# DSP_Lab_SS21_Mainboard.net
KiCad netlist of a schematic drawn in EAGLE
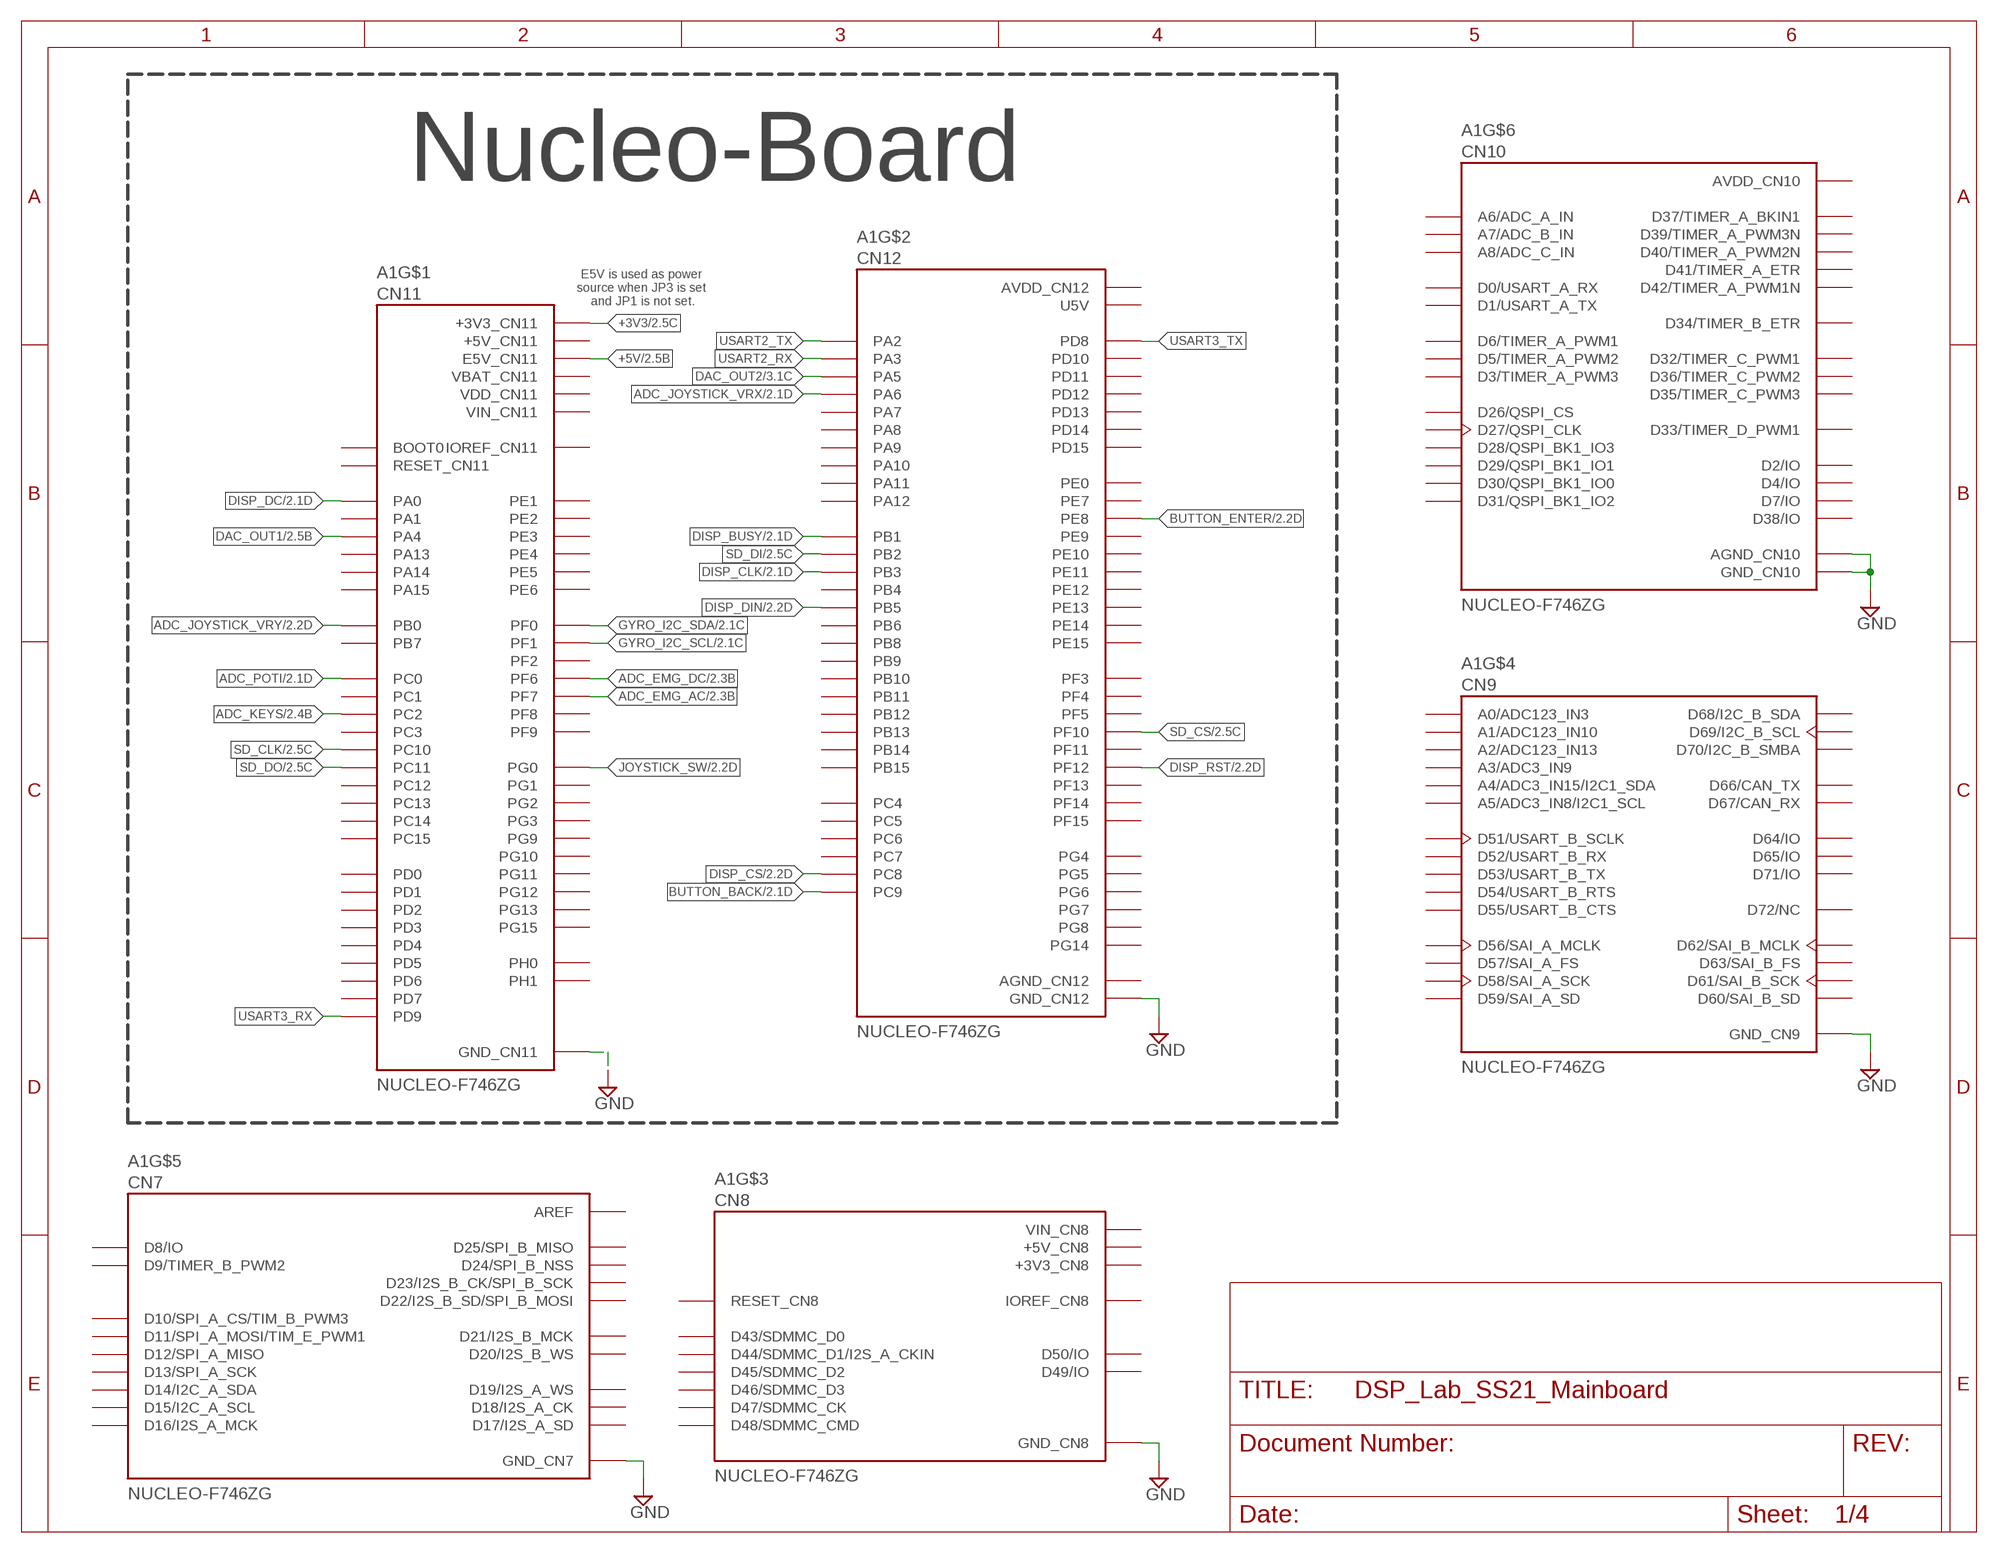
[diagram p0: schematic, sheet 1]
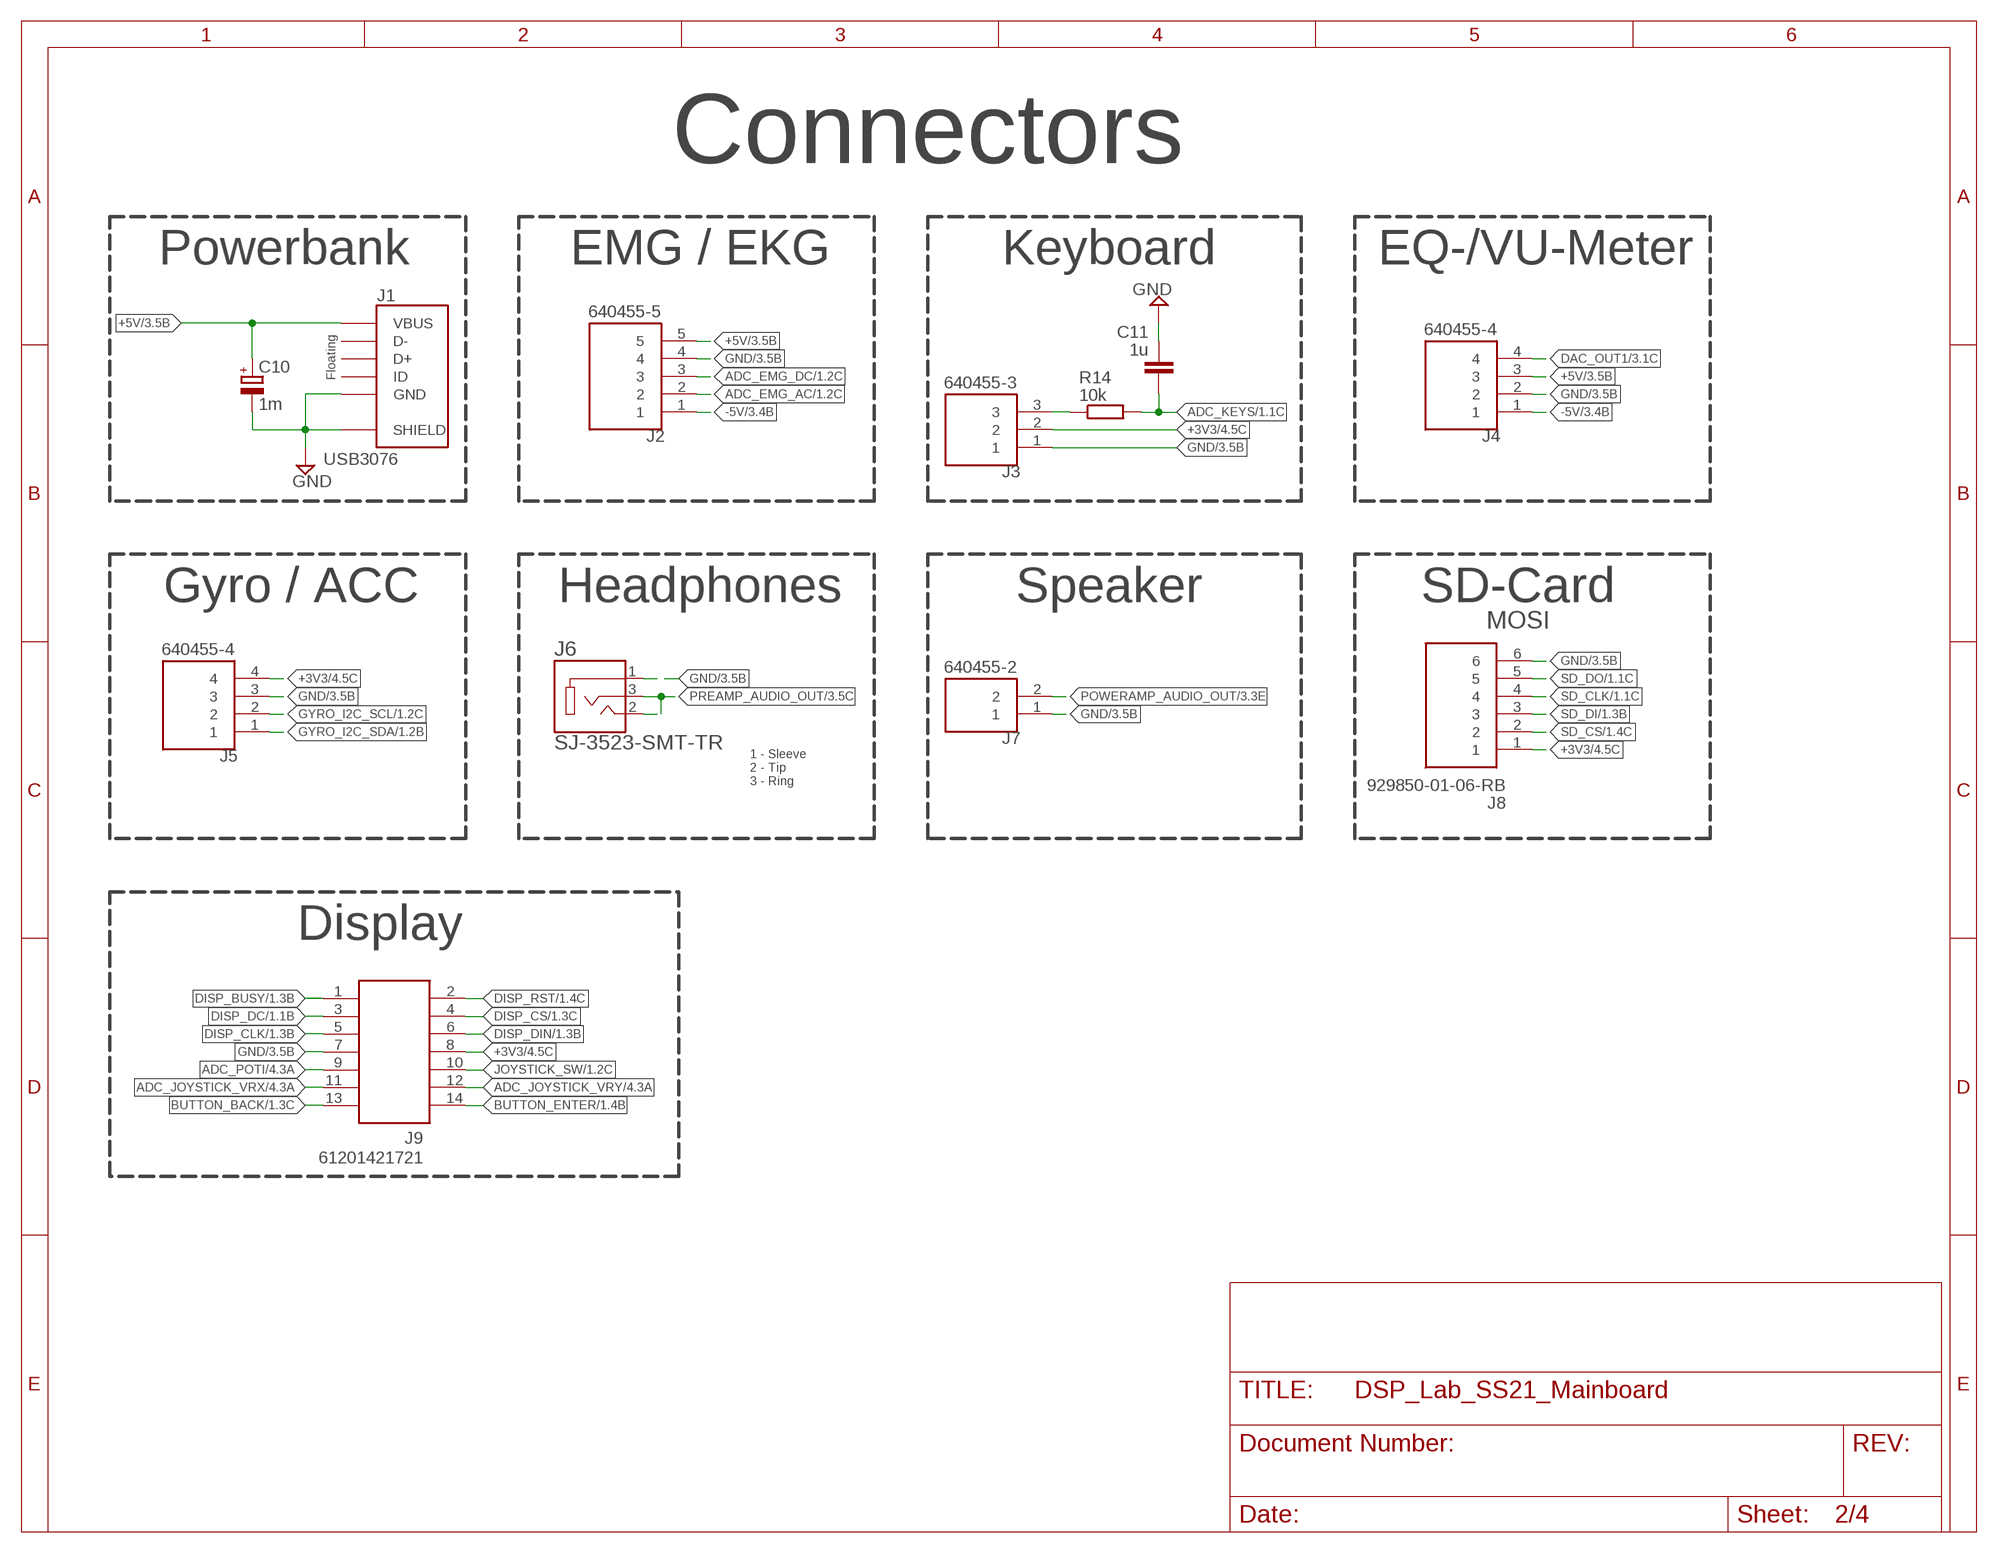
[diagram p1: schematic, sheet 2]
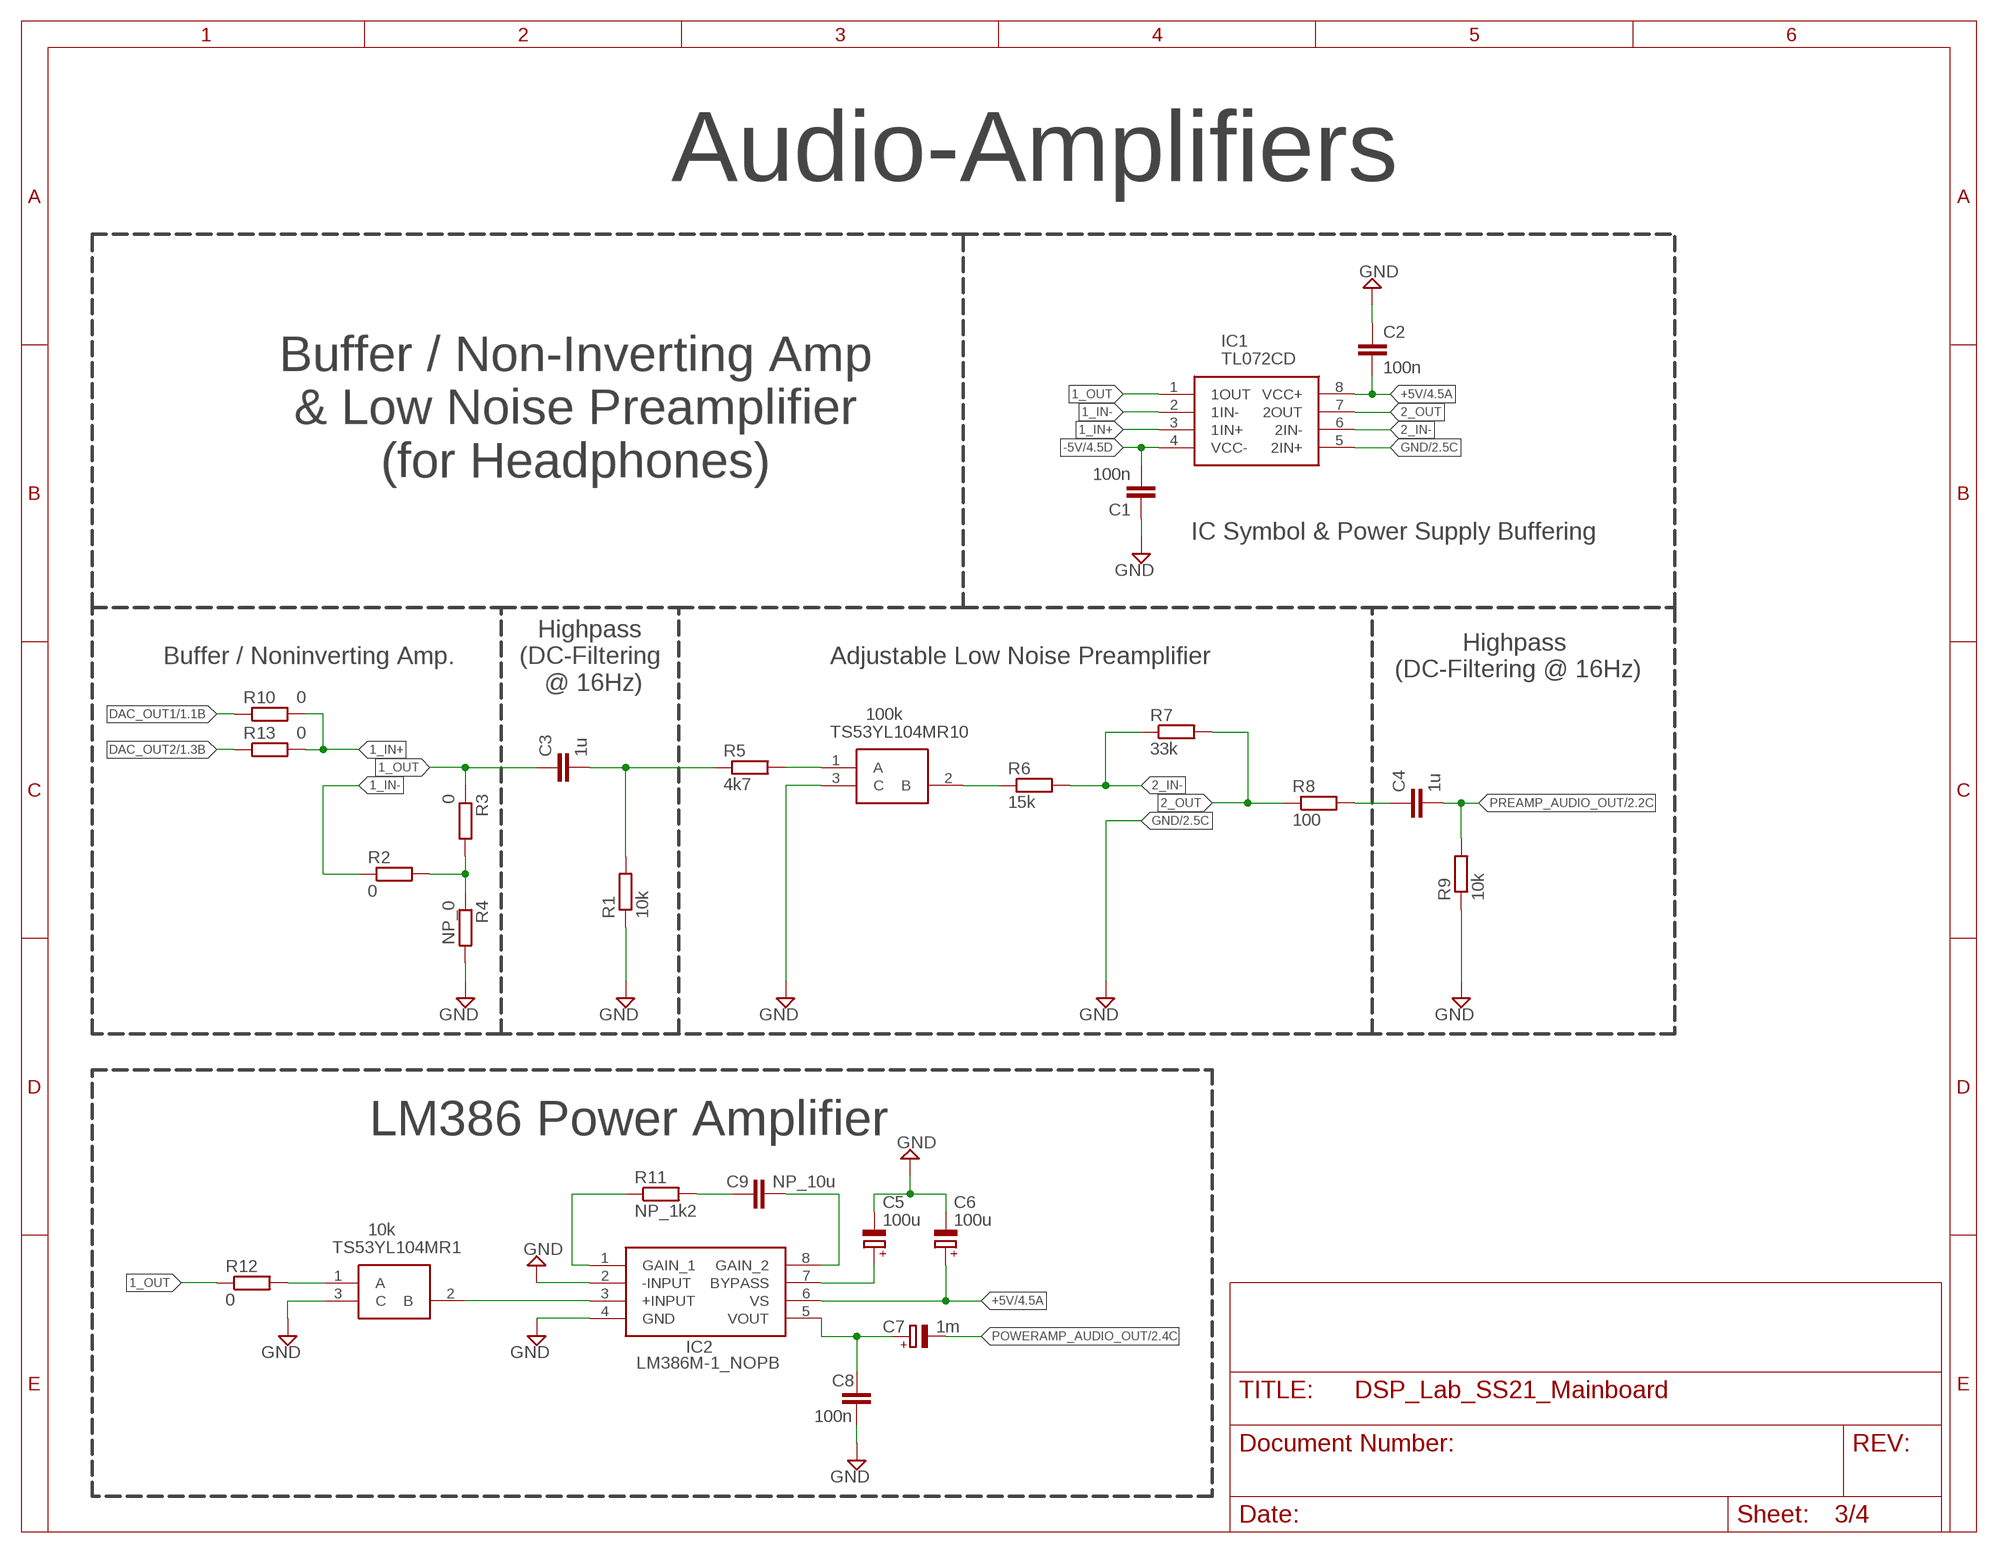
[diagram p2: schematic, sheet 3]
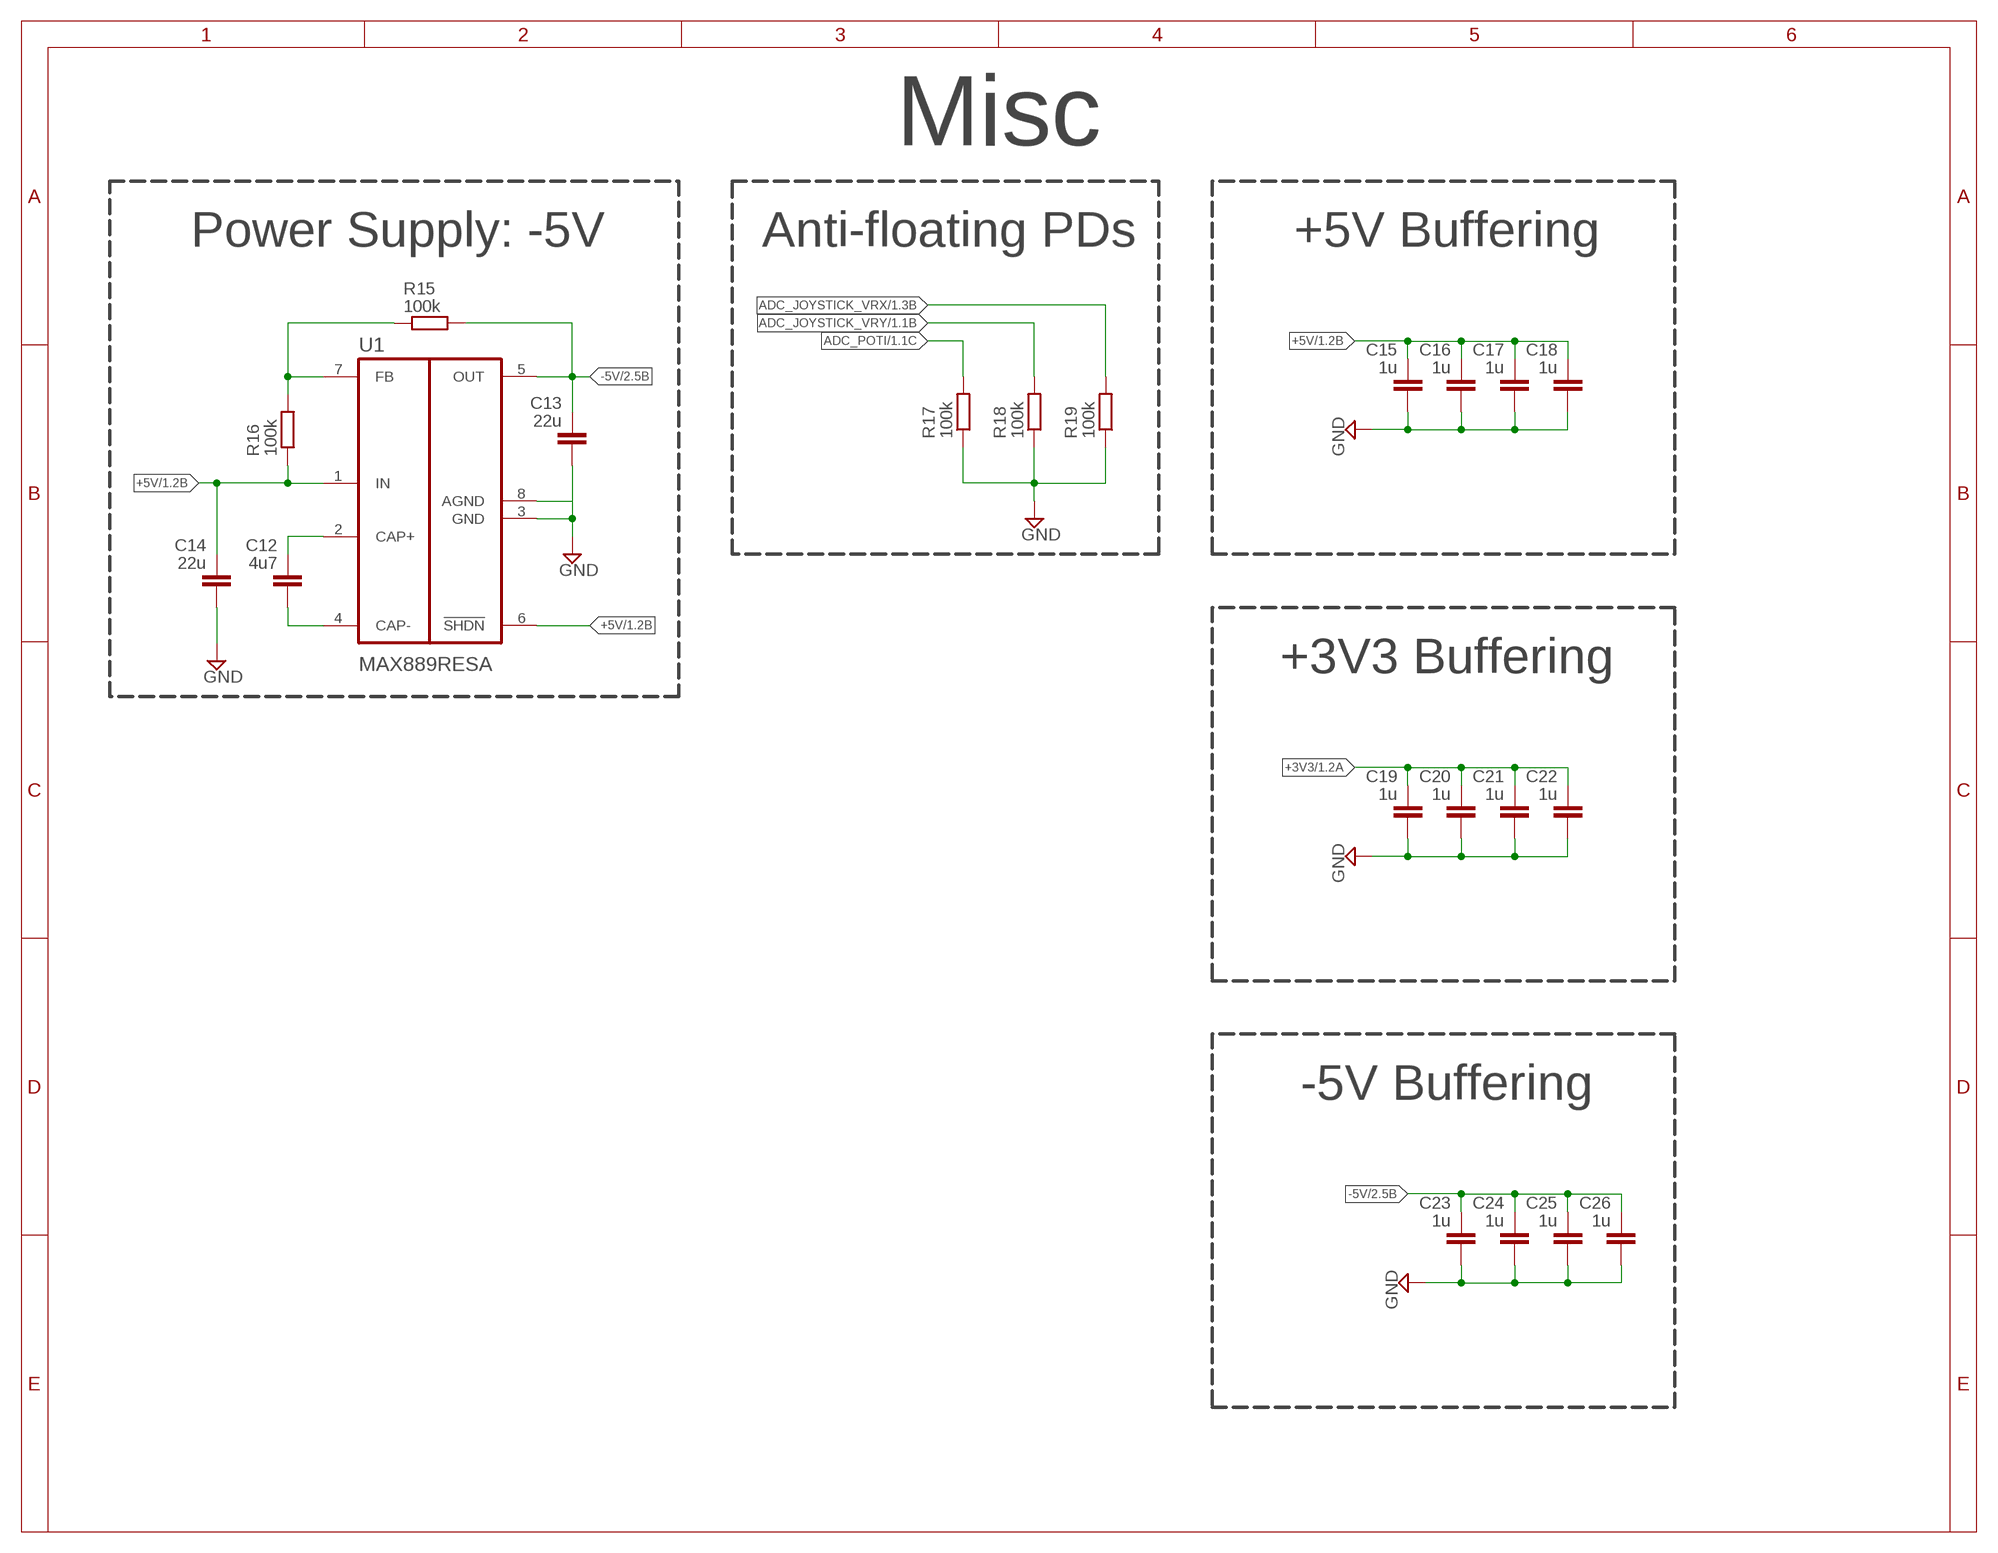
[diagram p3: schematic, sheet 4]

(export (version "E")
  (design (tool "Eeschema 10.0.6"))
  (components
    (comp (ref "C1")
      (value "100n")
      (footprint "eagle-import:C0603")
      (libsource (lib "eagle-import") (part "C-EUC0603"))
    )
    (comp (ref "C2")
      (value "100n")
      (footprint "eagle-import:C0603")
      (libsource (lib "eagle-import") (part "C-EUC0603"))
    )
    (comp (ref "C3")
      (value "1u")
      (footprint "eagle-import:C0603")
      (libsource (lib "eagle-import") (part "C-EUC0603"))
    )
    (comp (ref "C4")
      (value "1u")
      (footprint "eagle-import:C0603")
      (libsource (lib "eagle-import") (part "C-EUC0603"))
    )
    (comp (ref "C5")
      (value "100u")
      (footprint "eagle-import:E2,5-5")
      (libsource (lib "eagle-import") (part "CPOL-EUE2.5-5"))
    )
    (comp (ref "C6")
      (value "100u")
      (footprint "eagle-import:E2,5-5")
      (libsource (lib "eagle-import") (part "CPOL-EUE2.5-5"))
    )
    (comp (ref "C7")
      (value "1m")
      (footprint "eagle-import:E2,5-5")
      (libsource (lib "eagle-import") (part "CPOL-EUE2.5-5"))
    )
    (comp (ref "C8")
      (value "100n")
      (footprint "eagle-import:C0603")
      (libsource (lib "eagle-import") (part "C-EUC0603"))
    )
    (comp (ref "C9")
      (value "NP_10u")
      (footprint "eagle-import:C0603")
      (libsource (lib "eagle-import") (part "C-EUC0603"))
    )
    (comp (ref "IC1")
      (value "TL072CD")
      (footprint "eagle-import:SOIC127P600X175-8N")
      (fields (field (name "MOUSER_PART_NUMBER") "595-TL072CD"))
      (libsource (lib "eagle-import") (part "TL072CD"))
    )
    (comp (ref "IC2")
      (value "LM386M-1_NOPB")
      (footprint "eagle-import:SOIC127P600X175-8N")
      (fields
        (field (name "MANUFACTURER_PART_NUMBER") "LM386M-1/NOPB")
        (field (name "MOUSER_PART_NUMBER") "926-LM386M-1/NOPB")
      )
      (libsource (lib "eagle-import") (part "LM386M-1_NOPB"))
    )
    (comp (ref "R1")
      (value "10k")
      (footprint "eagle-import:R0603")
      (libsource (lib "eagle-import") (part "R-EU_R0603"))
    )
    (comp (ref "R2")
      (value "0")
      (footprint "eagle-import:R0603")
      (libsource (lib "eagle-import") (part "R-EU_R0603"))
    )
    (comp (ref "R3")
      (value "0")
      (footprint "eagle-import:R0603")
      (libsource (lib "eagle-import") (part "R-EU_R0603"))
    )
    (comp (ref "R4")
      (value "NP_0")
      (footprint "eagle-import:R0603")
      (libsource (lib "eagle-import") (part "R-EU_R0603"))
    )
    (comp (ref "R5")
      (value "4k7")
      (footprint "eagle-import:R0603")
      (libsource (lib "eagle-import") (part "R-EU_R0603"))
    )
    (comp (ref "R6")
      (value "15k")
      (footprint "eagle-import:R0603")
      (libsource (lib "eagle-import") (part "R-EU_R0603"))
    )
    (comp (ref "R7")
      (value "33k")
      (footprint "eagle-import:R0603")
      (libsource (lib "eagle-import") (part "R-EU_R0603"))
    )
    (comp (ref "R8")
      (value "100")
      (footprint "eagle-import:R0603")
      (libsource (lib "eagle-import") (part "R-EU_R0603"))
    )
    (comp (ref "R9")
      (value "10k")
      (footprint "eagle-import:R0603")
      (libsource (lib "eagle-import") (part "R-EU_R0603"))
    )
    (comp (ref "R10")
      (value "0")
      (footprint "eagle-import:R0603")
      (libsource (lib "eagle-import") (part "R-EU_R0603"))
    )
    (comp (ref "R11")
      (value "NP_1k2")
      (footprint "eagle-import:R0603")
      (libsource (lib "eagle-import") (part "R-EU_R0603"))
    )
    (comp (ref "R12")
      (value "0")
      (footprint "eagle-import:R0603")
      (libsource (lib "eagle-import") (part "R-EU_R0603"))
    )
    (comp (ref "R13")
      (value "0")
      (footprint "eagle-import:R0603")
      (libsource (lib "eagle-import") (part "R-EU_R0603"))
    )
    (comp (ref "TS53YL104MR1")
      (value "10k")
      (footprint "eagle-import:TS53YL203MR10")
      (fields
        (field (name "MANUFACTURER_PART_NUMBER") "TS53YL203MR10")
        (field (name "MOUSER_PART_NUMBER") "72-TS53YL-20K")
      )
      (libsource (lib "eagle-import") (part "TS53YL203MR10"))
    )
    (comp (ref "TS53YL104MR10")
      (value "100k")
      (footprint "eagle-import:TS53YL203MR10")
      (fields
        (field (name "MANUFACTURER_PART_NUMBER") "TS53YL203MR10")
        (field (name "MOUSER_PART_NUMBER") "72-TS53YL-20K")
      )
      (libsource (lib "eagle-import") (part "TS53YL203MR10"))
    )
    (comp (ref "C10")
      (value "1m")
      (footprint "eagle-import:E2,5-5")
      (libsource (lib "eagle-import") (part "CPOL-EUE2.5-5"))
    )
    (comp (ref "C11")
      (value "1u")
      (footprint "eagle-import:C0603")
      (libsource (lib "eagle-import") (part "C-EUC0603"))
    )
    (comp (ref "J1")
      (value "USB3076")
      (footprint "eagle-import:GCT_USB3076-XX-X_REVC")
      (fields (field (name "MF") "Global Connector Technology") (field (name "MP") "USB3076-30-A"))
      (libsource (lib "eagle-import") (part "USB3076-XX-X_REVC"))
    )
    (comp (ref "J2")
      (value "640455-5")
      (footprint "eagle-import:TE_640455-5")
      (fields (field (name "DIGI-KEY_PART_NUMBER") "A19453-ND") (field (name "MF") "TE Connectivity"))
      (libsource (lib "eagle-import") (part "640455-5"))
    )
    (comp (ref "J3")
      (value "640455-3")
      (footprint "eagle-import:TE_640455-3")
      (fields (field (name "MF") "TE Connectivity"))
      (libsource (lib "eagle-import") (part "640455-3"))
    )
    (comp (ref "J4")
      (value "640455-4")
      (footprint "eagle-import:TE_640455-4")
      (fields (field (name "MF") "TE Connectivity"))
      (libsource (lib "eagle-import") (part "640455-4"))
    )
    (comp (ref "J5")
      (value "640455-4")
      (footprint "eagle-import:TE_640455-4")
      (fields (field (name "MF") "TE Connectivity"))
      (libsource (lib "eagle-import") (part "640455-4"))
    )
    (comp (ref "J6")
      (value "SJ-3523-SMT-TR")
      (footprint "eagle-import:CUI_SJ-3523-SMT-TR")
      (fields (field (name "MF") "CUI Devices"))
      (libsource (lib "eagle-import") (part "SJ-3523-SMT-TR"))
    )
    (comp (ref "J7")
      (value "640455-2")
      (footprint "eagle-import:TE_640455-2")
      (fields (field (name "MF") "TE Connectivity"))
      (libsource (lib "eagle-import") (part "640455-2"))
    )
    (comp (ref "J8")
      (value "929850-01-06-RB")
      (footprint "eagle-import:RHDR6W76P0X254_1X6_1524X254X82")
      (fields (field (name "MOUSER_PART_NUMBER") "517-929850-01-06-RB"))
      (libsource (lib "eagle-import") (part "929850-01-06-RB"))
    )
    (comp (ref "J9")
      (value "61201421721")
      (footprint "eagle-import:61201421721")
      (fields (field (name "MF") "Würth Elektronik"))
      (libsource (lib "eagle-import") (part "61201421721"))
    )
    (comp (ref "R14")
      (value "10k")
      (footprint "eagle-import:R0603")
      (libsource (lib "eagle-import") (part "R-EU_R0603"))
    )
    (comp (ref "A1")
      (value "NUCLEO-F746ZG")
      (footprint "eagle-import:MODULE_NUCLEO-F746ZG")
      (fields (field (name "MF") "STMicroelectronics"))
      (libsource (lib "eagle-import") (part "NUCLEO-F746ZG"))
    )
    (comp (ref "C12")
      (value "4u7")
      (footprint "eagle-import:C0603")
      (libsource (lib "eagle-import") (part "C-EUC0603"))
    )
    (comp (ref "C13")
      (value "22u")
      (footprint "eagle-import:C0603")
      (libsource (lib "eagle-import") (part "C-EUC0603"))
    )
    (comp (ref "C14")
      (value "22u")
      (footprint "eagle-import:C0603")
      (libsource (lib "eagle-import") (part "C-EUC0603"))
    )
    (comp (ref "C15")
      (value "1u")
      (footprint "eagle-import:C0603")
      (libsource (lib "eagle-import") (part "C-EUC0603"))
    )
    (comp (ref "C16")
      (value "1u")
      (footprint "eagle-import:C0603")
      (libsource (lib "eagle-import") (part "C-EUC0603"))
    )
    (comp (ref "C17")
      (value "1u")
      (footprint "eagle-import:C0603")
      (libsource (lib "eagle-import") (part "C-EUC0603"))
    )
    (comp (ref "C18")
      (value "1u")
      (footprint "eagle-import:C0603")
      (libsource (lib "eagle-import") (part "C-EUC0603"))
    )
    (comp (ref "C19")
      (value "1u")
      (footprint "eagle-import:C0603")
      (libsource (lib "eagle-import") (part "C-EUC0603"))
    )
    (comp (ref "C20")
      (value "1u")
      (footprint "eagle-import:C0603")
      (libsource (lib "eagle-import") (part "C-EUC0603"))
    )
    (comp (ref "C21")
      (value "1u")
      (footprint "eagle-import:C0603")
      (libsource (lib "eagle-import") (part "C-EUC0603"))
    )
    (comp (ref "C22")
      (value "1u")
      (footprint "eagle-import:C0603")
      (libsource (lib "eagle-import") (part "C-EUC0603"))
    )
    (comp (ref "C23")
      (value "1u")
      (footprint "eagle-import:C0603")
      (libsource (lib "eagle-import") (part "C-EUC0603"))
    )
    (comp (ref "C24")
      (value "1u")
      (footprint "eagle-import:C0603")
      (libsource (lib "eagle-import") (part "C-EUC0603"))
    )
    (comp (ref "C25")
      (value "1u")
      (footprint "eagle-import:C0603")
      (libsource (lib "eagle-import") (part "C-EUC0603"))
    )
    (comp (ref "C26")
      (value "1u")
      (footprint "eagle-import:C0603")
      (libsource (lib "eagle-import") (part "C-EUC0603"))
    )
    (comp (ref "R15")
      (value "100k")
      (footprint "eagle-import:R0603")
      (libsource (lib "eagle-import") (part "R-EU_R0603"))
    )
    (comp (ref "R16")
      (value "100k")
      (footprint "eagle-import:R0603")
      (libsource (lib "eagle-import") (part "R-EU_R0603"))
    )
    (comp (ref "R17")
      (value "100k")
      (footprint "eagle-import:R0603")
      (libsource (lib "eagle-import") (part "R-EU_R0603"))
    )
    (comp (ref "R18")
      (value "100k")
      (footprint "eagle-import:R0603")
      (libsource (lib "eagle-import") (part "R-EU_R0603"))
    )
    (comp (ref "R19")
      (value "100k")
      (footprint "eagle-import:R0603")
      (libsource (lib "eagle-import") (part "R-EU_R0603"))
    )
    (comp (ref "U1")
      (value "MAX889RESA")
      (footprint "eagle-import:SOIC127P600X175-8N")
      (fields (field (name "MF") "Maxim Integrated") (field (name "MP") "MAX889RESA+"))
      (libsource (lib "eagle-import") (part "MAX889RESA"))
    )
  )
  (nets
    (net (code "1") (name "+3V3") (class "Default")
      (node (ref "A1") (pin "CN11_16") (pinfunction "+3V3_CN11_CN11_16") (pintype "power_in"))
      (node (ref "C19") (pin "2") (pinfunction "2_2") (pintype "passive"))
      (node (ref "C20") (pin "2") (pinfunction "2_2") (pintype "passive"))
      (node (ref "C21") (pin "2") (pinfunction "2_2") (pintype "passive"))
      (node (ref "C22") (pin "2") (pinfunction "2_2") (pintype "passive"))
      (node (ref "J3") (pin "2") (pinfunction "2_2") (pintype "passive"))
      (node (ref "J5") (pin "4") (pinfunction "4_4") (pintype "passive"))
      (node (ref "J8") (pin "1") (pinfunction "1_1") (pintype "bidirectional"))
      (node (ref "J9") (pin "8") (pinfunction "8_8") (pintype "passive"))
    )
    (net (code "2") (name "+3V3_CN8") (class "Default")
      (node (ref "A1") (pin "CN8_7") (pinfunction "+3V3_CN8_CN8_7") (pintype "power_in"))
    )
    (net (code "3") (name "+5V") (class "Default")
      (node (ref "A1") (pin "CN11_6") (pinfunction "E5V_CN11_CN11_6") (pintype "power_in"))
      (node (ref "C10") (pin "+") (pinfunction "+_+") (pintype "passive"))
      (node (ref "C14") (pin "2") (pinfunction "2_2") (pintype "passive"))
      (node (ref "C15") (pin "2") (pinfunction "2_2") (pintype "passive"))
      (node (ref "C16") (pin "2") (pinfunction "2_2") (pintype "passive"))
      (node (ref "C17") (pin "2") (pinfunction "2_2") (pintype "passive"))
      (node (ref "C18") (pin "2") (pinfunction "2_2") (pintype "passive"))
      (node (ref "C2") (pin "2") (pinfunction "2_2") (pintype "passive"))
      (node (ref "C6") (pin "+") (pinfunction "+_+") (pintype "passive"))
      (node (ref "IC1") (pin "8") (pinfunction "VCC+_8") (pintype "power_in"))
      (node (ref "IC2") (pin "6") (pinfunction "VS_6") (pintype "bidirectional"))
      (node (ref "J1") (pin "1") (pinfunction "VBUS_1") (pintype "power_in"))
      (node (ref "J2") (pin "5") (pinfunction "5_5") (pintype "passive"))
      (node (ref "J4") (pin "3") (pinfunction "3_3") (pintype "passive"))
      (node (ref "R16") (pin "1") (pinfunction "1_1") (pintype "passive"))
      (node (ref "U1") (pin "1") (pinfunction "IN_1") (pintype "input"))
      (node (ref "U1") (pin "6") (pinfunction "~{SHDN}_6") (pintype "input"))
    )
    (net (code "4") (name "+5V_CN8") (class "Default")
      (node (ref "A1") (pin "CN8_9") (pinfunction "+5V_CN8_CN8_9") (pintype "power_in"))
    )
    (net (code "5") (name "+5V_CN11") (class "Default")
      (node (ref "A1") (pin "CN11_18") (pinfunction "+5V_CN11_CN11_18") (pintype "power_in"))
    )
    (net (code "6") (name "-5V") (class "Default")
      (node (ref "C1") (pin "2") (pinfunction "2_2") (pintype "passive"))
      (node (ref "C13") (pin "2") (pinfunction "2_2") (pintype "passive"))
      (node (ref "C23") (pin "2") (pinfunction "2_2") (pintype "passive"))
      (node (ref "C24") (pin "2") (pinfunction "2_2") (pintype "passive"))
      (node (ref "C25") (pin "2") (pinfunction "2_2") (pintype "passive"))
      (node (ref "C26") (pin "2") (pinfunction "2_2") (pintype "passive"))
      (node (ref "IC1") (pin "4") (pinfunction "VCC-_4") (pintype "power_in"))
      (node (ref "J2") (pin "1") (pinfunction "1_1") (pintype "passive"))
      (node (ref "J4") (pin "1") (pinfunction "1_1") (pintype "passive"))
      (node (ref "R15") (pin "2") (pinfunction "2_2") (pintype "passive"))
      (node (ref "U1") (pin "5") (pinfunction "OUT_5") (pintype "output"))
    )
    (net (code "7") (name "1_IN+") (class "Default")
      (node (ref "IC1") (pin "3") (pinfunction "1IN+_3") (pintype "input"))
      (node (ref "R10") (pin "2") (pinfunction "2_2") (pintype "passive"))
      (node (ref "R13") (pin "2") (pinfunction "2_2") (pintype "passive"))
    )
    (net (code "8") (name "1_IN-") (class "Default")
      (node (ref "IC1") (pin "2") (pinfunction "1IN-_2") (pintype "input"))
      (node (ref "R2") (pin "1") (pinfunction "1_1") (pintype "passive"))
    )
    (net (code "9") (name "1_OUT") (class "Default")
      (node (ref "C3") (pin "1") (pinfunction "1_1") (pintype "passive"))
      (node (ref "IC1") (pin "1") (pinfunction "1OUT_1") (pintype "output"))
      (node (ref "R12") (pin "1") (pinfunction "1_1") (pintype "passive"))
      (node (ref "R3") (pin "1") (pinfunction "1_1") (pintype "passive"))
    )
    (net (code "10") (name "2_IN-") (class "Default")
      (node (ref "IC1") (pin "6") (pinfunction "2IN-_6") (pintype "input"))
      (node (ref "R6") (pin "2") (pinfunction "2_2") (pintype "passive"))
      (node (ref "R7") (pin "1") (pinfunction "1_1") (pintype "passive"))
    )
    (net (code "11") (name "2_OUT") (class "Default")
      (node (ref "IC1") (pin "7") (pinfunction "2OUT_7") (pintype "output"))
      (node (ref "R7") (pin "2") (pinfunction "2_2") (pintype "passive"))
      (node (ref "R8") (pin "1") (pinfunction "1_1") (pintype "passive"))
    )
    (net (code "12") (name "ADC_EMG_AC") (class "Default")
      (node (ref "A1") (pin "CN11_11") (pinfunction "PF7_CN11_11") (pintype "bidirectional"))
      (node (ref "J2") (pin "2") (pinfunction "2_2") (pintype "passive"))
    )
    (net (code "13") (name "ADC_EMG_DC") (class "Default")
      (node (ref "A1") (pin "CN11_9") (pinfunction "PF6_CN11_9") (pintype "bidirectional"))
      (node (ref "J2") (pin "3") (pinfunction "3_3") (pintype "passive"))
    )
    (net (code "14") (name "ADC_JOYSTICK_VRX") (class "Default")
      (node (ref "A1") (pin "CN12_13") (pinfunction "PA6_CN12_13") (pintype "bidirectional"))
      (node (ref "J9") (pin "11") (pinfunction "11_11") (pintype "passive"))
      (node (ref "R19") (pin "2") (pinfunction "2_2") (pintype "passive"))
    )
    (net (code "15") (name "ADC_JOYSTICK_VRY") (class "Default")
      (node (ref "A1") (pin "CN11_34") (pinfunction "PB0_CN11_34") (pintype "bidirectional"))
      (node (ref "J9") (pin "12") (pinfunction "12_12") (pintype "passive"))
      (node (ref "R18") (pin "2") (pinfunction "2_2") (pintype "passive"))
    )
    (net (code "16") (name "ADC_KEYS") (class "Default")
      (node (ref "A1") (pin "CN11_35") (pinfunction "PC2_CN11_35") (pintype "bidirectional"))
      (node (ref "C11") (pin "1") (pinfunction "1_1") (pintype "passive"))
      (node (ref "R14") (pin "2") (pinfunction "2_2") (pintype "passive"))
    )
    (net (code "17") (name "ADC_POTI") (class "Default")
      (node (ref "A1") (pin "CN11_38") (pinfunction "PC0_CN11_38") (pintype "bidirectional"))
      (node (ref "J9") (pin "9") (pinfunction "9_9") (pintype "passive"))
      (node (ref "R17") (pin "2") (pinfunction "2_2") (pintype "passive"))
    )
    (net (code "18") (name "AGND_CN12") (class "Default")
      (node (ref "A1") (pin "CN12_32") (pinfunction "AGND_CN12_CN12_32") (pintype "power_in"))
    )
    (net (code "19") (name "AREF") (class "Default")
      (node (ref "A1") (pin "CN7_6") (pinfunction "AREF_CN7_6") (pintype "power_in"))
    )
    (net (code "20") (name "AVDD_CN10") (class "Default")
      (node (ref "A1") (pin "CN10_1") (pinfunction "AVDD_CN10_CN10_1") (pintype "power_in"))
    )
    (net (code "21") (name "AVDD_CN12") (class "Default")
      (node (ref "A1") (pin "CN12_7") (pinfunction "AVDD_CN12_CN12_7") (pintype "power_in"))
    )
    (net (code "22") (name "BUTTON_BACK") (class "Default")
      (node (ref "A1") (pin "CN12_1") (pinfunction "PC9_CN12_1") (pintype "bidirectional"))
      (node (ref "J9") (pin "13") (pinfunction "13_13") (pintype "passive"))
    )
    (net (code "23") (name "BUTTON_ENTER") (class "Default")
      (node (ref "A1") (pin "CN12_40") (pinfunction "PE8_CN12_40") (pintype "bidirectional"))
      (node (ref "J9") (pin "14") (pinfunction "14_14") (pintype "passive"))
    )
    (net (code "24") (name "DAC_OUT1") (class "Default")
      (node (ref "A1") (pin "CN11_32") (pinfunction "PA4_CN11_32") (pintype "bidirectional"))
      (node (ref "J4") (pin "4") (pinfunction "4_4") (pintype "passive"))
      (node (ref "R10") (pin "1") (pinfunction "1_1") (pintype "passive"))
    )
    (net (code "25") (name "DAC_OUT2") (class "Default")
      (node (ref "A1") (pin "CN12_11") (pinfunction "PA5_CN12_11") (pintype "bidirectional"))
      (node (ref "R13") (pin "1") (pinfunction "1_1") (pintype "passive"))
    )
    (net (code "26") (name "DISP_BUSY") (class "Default")
      (node (ref "A1") (pin "CN12_24") (pinfunction "PB1_CN12_24") (pintype "bidirectional"))
      (node (ref "J9") (pin "1") (pinfunction "1_1") (pintype "passive"))
    )
    (net (code "27") (name "DISP_CLK") (class "Default")
      (node (ref "A1") (pin "CN12_31") (pinfunction "PB3_CN12_31") (pintype "bidirectional"))
      (node (ref "J9") (pin "5") (pinfunction "5_5") (pintype "passive"))
    )
    (net (code "28") (name "DISP_CS") (class "Default")
      (node (ref "A1") (pin "CN12_2") (pinfunction "PC8_CN12_2") (pintype "bidirectional"))
      (node (ref "J9") (pin "4") (pinfunction "4_4") (pintype "passive"))
    )
    (net (code "29") (name "DISP_DC") (class "Default")
      (node (ref "A1") (pin "CN11_28") (pinfunction "PA0_CN11_28") (pintype "bidirectional"))
      (node (ref "J9") (pin "3") (pinfunction "3_3") (pintype "passive"))
    )
    (net (code "30") (name "DISP_DIN") (class "Default")
      (node (ref "A1") (pin "CN12_29") (pinfunction "PB5_CN12_29") (pintype "bidirectional"))
      (node (ref "J9") (pin "6") (pinfunction "6_6") (pintype "passive"))
    )
    (net (code "31") (name "DISP_RST") (class "Default")
      (node (ref "A1") (pin "CN12_59") (pinfunction "PF12_CN12_59") (pintype "bidirectional"))
      (node (ref "J9") (pin "2") (pinfunction "2_2") (pintype "passive"))
    )
    (net (code "32") (name "GND") (class "Default")
      (node (ref "A1") (pin "CN10_17") (pinfunction "GND_CN10_CN10_17") (pintype "power_in"))
      (node (ref "A1") (pin "CN10_22") (pinfunction "GND_CN10_CN10_22") (pintype "power_in"))
      (node (ref "A1") (pin "CN10_27") (pinfunction "GND_CN10_CN10_27") (pintype "power_in"))
      (node (ref "A1") (pin "CN10_3") (pinfunction "AGND_CN10_CN10_3") (pintype "power_in"))
      (node (ref "A1") (pin "CN10_5") (pinfunction "GND_CN10_CN10_5") (pintype "power_in"))
      (node (ref "A1") (pin "CN11_19") (pinfunction "GND_CN11_CN11_19") (pintype "power_in"))
      (node (ref "A1") (pin "CN11_20") (pinfunction "GND_CN11_CN11_20") (pintype "power_in"))
      (node (ref "A1") (pin "CN11_22") (pinfunction "GND_CN11_CN11_22") (pintype "power_in"))
      (node (ref "A1") (pin "CN11_49") (pinfunction "GND_CN11_CN11_49") (pintype "power_in"))
      (node (ref "A1") (pin "CN11_60") (pinfunction "GND_CN11_CN11_60") (pintype "power_in"))
      (node (ref "A1") (pin "CN11_71") (pinfunction "GND_CN11_CN11_71") (pintype "power_in"))
      (node (ref "A1") (pin "CN11_72") (pinfunction "GND_CN11_CN11_72") (pintype "power_in"))
      (node (ref "A1") (pin "CN11_8") (pinfunction "GND_CN11_CN11_8") (pintype "power_in"))
      (node (ref "A1") (pin "CN12_20") (pinfunction "GND_CN12_CN12_20") (pintype "power_in"))
      (node (ref "A1") (pin "CN12_39") (pinfunction "GND_CN12_CN12_39") (pintype "power_in"))
      (node (ref "A1") (pin "CN12_54") (pinfunction "GND_CN12_CN12_54") (pintype "power_in"))
      (node (ref "A1") (pin "CN12_63") (pinfunction "GND_CN12_CN12_63") (pintype "power_in"))
      (node (ref "A1") (pin "CN12_71") (pinfunction "GND_CN12_CN12_71") (pintype "power_in"))
      (node (ref "A1") (pin "CN12_72") (pinfunction "GND_CN12_CN12_72") (pintype "power_in"))
      (node (ref "A1") (pin "CN12_9") (pinfunction "GND_CN12_CN12_9") (pintype "power_in"))
      (node (ref "A1") (pin "CN7_8") (pinfunction "GND_CN7_CN7_8") (pintype "power_in"))
      (node (ref "A1") (pin "CN8_11") (pinfunction "GND_CN8_CN8_11") (pintype "power_in"))
      (node (ref "A1") (pin "CN8_13") (pinfunction "GND_CN8_CN8_13") (pintype "power_in"))
      (node (ref "A1") (pin "CN9_12") (pinfunction "GND_CN9_CN9_12") (pintype "power_in"))
      (node (ref "A1") (pin "CN9_23") (pinfunction "GND_CN9_CN9_23") (pintype "power_in"))
      (node (ref "C1") (pin "1") (pinfunction "1_1") (pintype "passive"))
      (node (ref "C10") (pin "-") (pinfunction "-_-") (pintype "passive"))
      (node (ref "C11") (pin "2") (pinfunction "2_2") (pintype "passive"))
      (node (ref "C13") (pin "1") (pinfunction "1_1") (pintype "passive"))
      (node (ref "C14") (pin "1") (pinfunction "1_1") (pintype "passive"))
      (node (ref "C15") (pin "1") (pinfunction "1_1") (pintype "passive"))
      (node (ref "C16") (pin "1") (pinfunction "1_1") (pintype "passive"))
      (node (ref "C17") (pin "1") (pinfunction "1_1") (pintype "passive"))
      (node (ref "C18") (pin "1") (pinfunction "1_1") (pintype "passive"))
      (node (ref "C19") (pin "1") (pinfunction "1_1") (pintype "passive"))
      (node (ref "C2") (pin "1") (pinfunction "1_1") (pintype "passive"))
      (node (ref "C20") (pin "1") (pinfunction "1_1") (pintype "passive"))
      (node (ref "C21") (pin "1") (pinfunction "1_1") (pintype "passive"))
      (node (ref "C22") (pin "1") (pinfunction "1_1") (pintype "passive"))
      (node (ref "C23") (pin "1") (pinfunction "1_1") (pintype "passive"))
      (node (ref "C24") (pin "1") (pinfunction "1_1") (pintype "passive"))
      (node (ref "C25") (pin "1") (pinfunction "1_1") (pintype "passive"))
      (node (ref "C26") (pin "1") (pinfunction "1_1") (pintype "passive"))
      (node (ref "C5") (pin "-") (pinfunction "-_-") (pintype "passive"))
      (node (ref "C6") (pin "-") (pinfunction "-_-") (pintype "passive"))
      (node (ref "C8") (pin "2") (pinfunction "2_2") (pintype "passive"))
      (node (ref "IC1") (pin "5") (pinfunction "2IN+_5") (pintype "input"))
      (node (ref "IC2") (pin "2") (pinfunction "-INPUT_2") (pintype "bidirectional"))
      (node (ref "IC2") (pin "4") (pinfunction "GND_4") (pintype "bidirectional"))
      (node (ref "J1") (pin "10") (pinfunction "SHIELD_10") (pintype "power_in"))
      (node (ref "J1") (pin "11") (pinfunction "SHIELD_11") (pintype "power_in"))
      (node (ref "J1") (pin "5") (pinfunction "GND_5") (pintype "power_in"))
      (node (ref "J1") (pin "6") (pinfunction "SHIELD_6") (pintype "power_in"))
      (node (ref "J1") (pin "7") (pinfunction "SHIELD_7") (pintype "power_in"))
      (node (ref "J1") (pin "8") (pinfunction "SHIELD_8") (pintype "power_in"))
      (node (ref "J1") (pin "9") (pinfunction "SHIELD_9") (pintype "power_in"))
      (node (ref "J2") (pin "4") (pinfunction "4_4") (pintype "passive"))
      (node (ref "J3") (pin "1") (pinfunction "1_1") (pintype "passive"))
      (node (ref "J4") (pin "2") (pinfunction "2_2") (pintype "passive"))
      (node (ref "J5") (pin "3") (pinfunction "3_3") (pintype "passive"))
      (node (ref "J6") (pin "1") (pinfunction "1_1") (pintype "passive"))
      (node (ref "J7") (pin "1") (pinfunction "1_1") (pintype "passive"))
      (node (ref "J8") (pin "6") (pinfunction "6_6") (pintype "bidirectional"))
      (node (ref "J9") (pin "7") (pinfunction "7_7") (pintype "passive"))
      (node (ref "R1") (pin "1") (pinfunction "1_1") (pintype "passive"))
      (node (ref "R17") (pin "1") (pinfunction "1_1") (pintype "passive"))
      (node (ref "R18") (pin "1") (pinfunction "1_1") (pintype "passive"))
      (node (ref "R19") (pin "1") (pinfunction "1_1") (pintype "passive"))
      (node (ref "R4") (pin "2") (pinfunction "2_2") (pintype "passive"))
      (node (ref "R9") (pin "1") (pinfunction "1_1") (pintype "passive"))
      (node (ref "TS53YL104MR1") (pin "3") (pinfunction "C_3") (pintype "bidirectional"))
      (node (ref "TS53YL104MR10") (pin "3") (pinfunction "C_3") (pintype "bidirectional"))
      (node (ref "U1") (pin "3") (pinfunction "GND_3") (pintype "power_in"))
      (node (ref "U1") (pin "8") (pinfunction "AGND_8") (pintype "power_in"))
    )
    (net (code "33") (name "GYRO_I2C_SCL") (class "Default")
      (node (ref "A1") (pin "CN11_51") (pinfunction "PF1_CN11_51") (pintype "bidirectional"))
      (node (ref "J5") (pin "2") (pinfunction "2_2") (pintype "passive"))
    )
    (net (code "34") (name "GYRO_I2C_SDA") (class "Default")
      (node (ref "A1") (pin "CN11_53") (pinfunction "PF0_CN11_53") (pintype "bidirectional"))
      (node (ref "J5") (pin "1") (pinfunction "1_1") (pintype "passive"))
    )
    (net (code "35") (name "JOYSTICK_SW") (class "Default")
      (node (ref "A1") (pin "CN11_59") (pinfunction "PG0_CN11_59") (pintype "bidirectional"))
      (node (ref "J9") (pin "10") (pinfunction "10_10") (pintype "passive"))
    )
    (net (code "36") (name "Net-(C3-Pad2)") (class "Default")
      (node (ref "C3") (pin "2") (pinfunction "2_2") (pintype "passive"))
      (node (ref "R1") (pin "2") (pinfunction "2_2") (pintype "passive"))
      (node (ref "R5") (pin "1") (pinfunction "1_1") (pintype "passive"))
    )
    (net (code "37") (name "Net-(C4-Pad1)") (class "Default")
      (node (ref "C4") (pin "1") (pinfunction "1_1") (pintype "passive"))
      (node (ref "R8") (pin "2") (pinfunction "2_2") (pintype "passive"))
    )
    (net (code "38") (name "Net-(C9-Pad1)") (class "Default")
      (node (ref "C9") (pin "1") (pinfunction "1_1") (pintype "passive"))
      (node (ref "R11") (pin "2") (pinfunction "2_2") (pintype "passive"))
    )
    (net (code "39") (name "Net-(IC2-+INPUT)") (class "Default")
      (node (ref "IC2") (pin "3") (pinfunction "+INPUT_3") (pintype "bidirectional"))
      (node (ref "TS53YL104MR1") (pin "2") (pinfunction "B_2") (pintype "bidirectional"))
    )
    (net (code "40") (name "Net-(IC2-BYPASS)") (class "Default")
      (node (ref "C5") (pin "+") (pinfunction "+_+") (pintype "passive"))
      (node (ref "IC2") (pin "7") (pinfunction "BYPASS_7") (pintype "bidirectional"))
    )
    (net (code "41") (name "Net-(IC2-GAIN_1)") (class "Default")
      (node (ref "IC2") (pin "1") (pinfunction "GAIN_1_1") (pintype "bidirectional"))
      (node (ref "R11") (pin "1") (pinfunction "1_1") (pintype "passive"))
    )
    (net (code "42") (name "Net-(IC2-GAIN_2)") (class "Default")
      (node (ref "C9") (pin "2") (pinfunction "2_2") (pintype "passive"))
      (node (ref "IC2") (pin "8") (pinfunction "GAIN_2_8") (pintype "bidirectional"))
    )
    (net (code "43") (name "Net-(IC2-VOUT)") (class "Default")
      (node (ref "C7") (pin "+") (pinfunction "+_+") (pintype "passive"))
      (node (ref "C8") (pin "1") (pinfunction "1_1") (pintype "passive"))
      (node (ref "IC2") (pin "5") (pinfunction "VOUT_5") (pintype "bidirectional"))
    )
    (net (code "44") (name "Net-(J3-Pad3)") (class "Default")
      (node (ref "J3") (pin "3") (pinfunction "3_3") (pintype "passive"))
      (node (ref "R14") (pin "1") (pinfunction "1_1") (pintype "passive"))
    )
    (net (code "45") (name "Net-(R2-Pad2)") (class "Default")
      (node (ref "R2") (pin "2") (pinfunction "2_2") (pintype "passive"))
      (node (ref "R3") (pin "2") (pinfunction "2_2") (pintype "passive"))
      (node (ref "R4") (pin "1") (pinfunction "1_1") (pintype "passive"))
    )
    (net (code "46") (name "Net-(TS53YL104MR1-A)") (class "Default")
      (node (ref "R12") (pin "2") (pinfunction "2_2") (pintype "passive"))
      (node (ref "TS53YL104MR1") (pin "1") (pinfunction "A_1") (pintype "bidirectional"))
    )
    (net (code "47") (name "Net-(TS53YL104MR10-A)") (class "Default")
      (node (ref "R5") (pin "2") (pinfunction "2_2") (pintype "passive"))
      (node (ref "TS53YL104MR10") (pin "1") (pinfunction "A_1") (pintype "bidirectional"))
    )
    (net (code "48") (name "Net-(TS53YL104MR10-B)") (class "Default")
      (node (ref "R6") (pin "1") (pinfunction "1_1") (pintype "passive"))
      (node (ref "TS53YL104MR10") (pin "2") (pinfunction "B_2") (pintype "bidirectional"))
    )
    (net (code "49") (name "Net-(U1-CAP+)") (class "Default")
      (node (ref "C12") (pin "2") (pinfunction "2_2") (pintype "passive"))
      (node (ref "U1") (pin "2") (pinfunction "CAP+_2") (pintype "bidirectional"))
    )
    (net (code "50") (name "Net-(U1-CAP-)") (class "Default")
      (node (ref "C12") (pin "1") (pinfunction "1_1") (pintype "passive"))
      (node (ref "U1") (pin "4") (pinfunction "CAP-_4") (pintype "bidirectional"))
    )
    (net (code "51") (name "Net-(U1-FB)") (class "Default")
      (node (ref "R15") (pin "1") (pinfunction "1_1") (pintype "passive"))
      (node (ref "R16") (pin "2") (pinfunction "2_2") (pintype "passive"))
      (node (ref "U1") (pin "7") (pinfunction "FB_7") (pintype "input"))
    )
    (net (code "52") (name "POWERAMP_AUDIO_OUT") (class "Default")
      (node (ref "C7") (pin "-") (pinfunction "-_-") (pintype "passive"))
      (node (ref "J7") (pin "2") (pinfunction "2_2") (pintype "passive"))
    )
    (net (code "53") (name "PREAMP_AUDIO_OUT") (class "Default")
      (node (ref "C4") (pin "2") (pinfunction "2_2") (pintype "passive"))
      (node (ref "J6") (pin "2") (pinfunction "2_2") (pintype "passive"))
      (node (ref "J6") (pin "3") (pinfunction "3_3") (pintype "passive"))
      (node (ref "R9") (pin "2") (pinfunction "2_2") (pintype "passive"))
    )
    (net (code "54") (name "SD_CLK") (class "Default")
      (node (ref "A1") (pin "CN11_1") (pinfunction "PC10_CN11_1") (pintype "bidirectional"))
      (node (ref "J8") (pin "4") (pinfunction "4_4") (pintype "bidirectional"))
    )
    (net (code "55") (name "SD_CS") (class "Default")
      (node (ref "A1") (pin "CN12_42") (pinfunction "PF10_CN12_42") (pintype "bidirectional"))
      (node (ref "J8") (pin "2") (pinfunction "2_2") (pintype "bidirectional"))
    )
    (net (code "56") (name "SD_DI") (class "Default")
      (node (ref "A1") (pin "CN12_22") (pinfunction "PB2_CN12_22") (pintype "bidirectional"))
      (node (ref "J8") (pin "3") (pinfunction "3_3") (pintype "bidirectional"))
    )
    (net (code "57") (name "SD_DO") (class "Default")
      (node (ref "A1") (pin "CN11_2") (pinfunction "PC11_CN11_2") (pintype "bidirectional"))
      (node (ref "J8") (pin "5") (pinfunction "5_5") (pintype "bidirectional"))
    )
    (net (code "58") (name "U5V") (class "Default")
      (node (ref "A1") (pin "CN12_8") (pinfunction "U5V_CN12_8") (pintype "power_in"))
    )
    (net (code "59") (name "USART2_RX") (class "Default")
      (node (ref "A1") (pin "CN12_37") (pinfunction "PA3_CN12_37") (pintype "bidirectional"))
    )
    (net (code "60") (name "USART2_TX") (class "Default")
      (node (ref "A1") (pin "CN12_35") (pinfunction "PA2_CN12_35") (pintype "bidirectional"))
    )
    (net (code "61") (name "USART3_RX") (class "Default")
      (node (ref "A1") (pin "CN11_69") (pinfunction "PD9_CN11_69") (pintype "bidirectional"))
    )
    (net (code "62") (name "USART3_TX") (class "Default")
      (node (ref "A1") (pin "CN12_10") (pinfunction "PD8_CN12_10") (pintype "bidirectional"))
    )
    (net (code "63") (name "VBAT_CN11") (class "Default")
      (node (ref "A1") (pin "CN11_33") (pinfunction "VBAT_CN11_CN11_33") (pintype "power_in"))
    )
    (net (code "64") (name "VDD_CN11") (class "Default")
      (node (ref "A1") (pin "CN11_5") (pinfunction "VDD_CN11_CN11_5") (pintype "power_in"))
    )
    (net (code "65") (name "VIN_CN8") (class "Default")
      (node (ref "A1") (pin "CN8_15") (pinfunction "VIN_CN8_CN8_15") (pintype "power_in"))
    )
    (net (code "66") (name "VIN_CN11") (class "Default")
      (node (ref "A1") (pin "CN11_24") (pinfunction "VIN_CN11_CN11_24") (pintype "power_in"))
    )
    (net (code "67") (name "unconnected-(A1A-BOOT0-PadCN11_7)") (class "Default")
      (node (ref "A1") (pin "CN11_7") (pinfunction "BOOT0_CN11_7") (pintype "bidirectional"))
    )
    (net (code "68") (name "unconnected-(A1A-IOREF_CN11-PadCN11_12)") (class "Default")
      (node (ref "A1") (pin "CN11_12") (pinfunction "IOREF_CN11_CN11_12") (pintype "bidirectional"))
    )
    (net (code "69") (name "unconnected-(A1A-PA1-PadCN11_30)") (class "Default")
      (node (ref "A1") (pin "CN11_30") (pinfunction "PA1_CN11_30") (pintype "bidirectional"))
    )
    (net (code "70") (name "unconnected-(A1A-PA13-PadCN11_13)") (class "Default")
      (node (ref "A1") (pin "CN11_13") (pinfunction "PA13_CN11_13") (pintype "bidirectional"))
    )
    (net (code "71") (name "unconnected-(A1A-PA14-PadCN11_15)") (class "Default")
      (node (ref "A1") (pin "CN11_15") (pinfunction "PA14_CN11_15") (pintype "bidirectional"))
    )
    (net (code "72") (name "unconnected-(A1A-PA15-PadCN11_17)") (class "Default")
      (node (ref "A1") (pin "CN11_17") (pinfunction "PA15_CN11_17") (pintype "bidirectional"))
    )
    (net (code "73") (name "unconnected-(A1A-PB7-PadCN11_21)") (class "Default")
      (node (ref "A1") (pin "CN11_21") (pinfunction "PB7_CN11_21") (pintype "bidirectional"))
    )
    (net (code "74") (name "unconnected-(A1A-PC1-PadCN11_36)") (class "Default")
      (node (ref "A1") (pin "CN11_36") (pinfunction "PC1_CN11_36") (pintype "bidirectional"))
    )
    (net (code "75") (name "unconnected-(A1A-PC3-PadCN11_37)") (class "Default")
      (node (ref "A1") (pin "CN11_37") (pinfunction "PC3_CN11_37") (pintype "bidirectional"))
    )
    (net (code "76") (name "unconnected-(A1A-PC12-PadCN11_3)") (class "Default")
      (node (ref "A1") (pin "CN11_3") (pinfunction "PC12_CN11_3") (pintype "bidirectional"))
    )
    (net (code "77") (name "unconnected-(A1A-PC13-PadCN11_23)") (class "Default")
      (node (ref "A1") (pin "CN11_23") (pinfunction "PC13_CN11_23") (pintype "bidirectional"))
    )
    (net (code "78") (name "unconnected-(A1A-PC14-PadCN11_25)") (class "Default")
      (node (ref "A1") (pin "CN11_25") (pinfunction "PC14_CN11_25") (pintype "bidirectional"))
    )
    (net (code "79") (name "unconnected-(A1A-PC15-PadCN11_27)") (class "Default")
      (node (ref "A1") (pin "CN11_27") (pinfunction "PC15_CN11_27") (pintype "bidirectional"))
    )
    (net (code "80") (name "unconnected-(A1A-PD0-PadCN11_57)") (class "Default")
      (node (ref "A1") (pin "CN11_57") (pinfunction "PD0_CN11_57") (pintype "bidirectional"))
    )
    (net (code "81") (name "unconnected-(A1A-PD1-PadCN11_55)") (class "Default")
      (node (ref "A1") (pin "CN11_55") (pinfunction "PD1_CN11_55") (pintype "bidirectional"))
    )
    (net (code "82") (name "unconnected-(A1A-PD2-PadCN11_4)") (class "Default")
      (node (ref "A1") (pin "CN11_4") (pinfunction "PD2_CN11_4") (pintype "bidirectional"))
    )
    (net (code "83") (name "unconnected-(A1A-PD3-PadCN11_40)") (class "Default")
      (node (ref "A1") (pin "CN11_40") (pinfunction "PD3_CN11_40") (pintype "bidirectional"))
    )
    (net (code "84") (name "unconnected-(A1A-PD4-PadCN11_39)") (class "Default")
      (node (ref "A1") (pin "CN11_39") (pinfunction "PD4_CN11_39") (pintype "bidirectional"))
    )
    (net (code "85") (name "unconnected-(A1A-PD5-PadCN11_41)") (class "Default")
      (node (ref "A1") (pin "CN11_41") (pinfunction "PD5_CN11_41") (pintype "bidirectional"))
    )
    (net (code "86") (name "unconnected-(A1A-PD6-PadCN11_43)") (class "Default")
      (node (ref "A1") (pin "CN11_43") (pinfunction "PD6_CN11_43") (pintype "bidirectional"))
    )
    (net (code "87") (name "unconnected-(A1A-PD7-PadCN11_45)") (class "Default")
      (node (ref "A1") (pin "CN11_45") (pinfunction "PD7_CN11_45") (pintype "bidirectional"))
    )
    (net (code "88") (name "unconnected-(A1A-PE1-PadCN11_61)") (class "Default")
      (node (ref "A1") (pin "CN11_61") (pinfunction "PE1_CN11_61") (pintype "bidirectional"))
    )
    (net (code "89") (name "unconnected-(A1A-PE2-PadCN11_46)") (class "Default")
      (node (ref "A1") (pin "CN11_46") (pinfunction "PE2_CN11_46") (pintype "bidirectional"))
    )
    (net (code "90") (name "unconnected-(A1A-PE3-PadCN11_47)") (class "Default")
      (node (ref "A1") (pin "CN11_47") (pinfunction "PE3_CN11_47") (pintype "bidirectional"))
    )
    (net (code "91") (name "unconnected-(A1A-PE4-PadCN11_48)") (class "Default")
      (node (ref "A1") (pin "CN11_48") (pinfunction "PE4_CN11_48") (pintype "bidirectional"))
    )
    (net (code "92") (name "unconnected-(A1A-PE5-PadCN11_50)") (class "Default")
      (node (ref "A1") (pin "CN11_50") (pinfunction "PE5_CN11_50") (pintype "bidirectional"))
    )
    (net (code "93") (name "unconnected-(A1A-PE6-PadCN11_62)") (class "Default")
      (node (ref "A1") (pin "CN11_62") (pinfunction "PE6_CN11_62") (pintype "bidirectional"))
    )
    (net (code "94") (name "unconnected-(A1A-PF2-PadCN11_52)") (class "Default")
      (node (ref "A1") (pin "CN11_52") (pinfunction "PF2_CN11_52") (pintype "bidirectional"))
    )
    (net (code "95") (name "unconnected-(A1A-PF8-PadCN11_54)") (class "Default")
      (node (ref "A1") (pin "CN11_54") (pinfunction "PF8_CN11_54") (pintype "bidirectional"))
    )
    (net (code "96") (name "unconnected-(A1A-PF9-PadCN11_56)") (class "Default")
      (node (ref "A1") (pin "CN11_56") (pinfunction "PF9_CN11_56") (pintype "bidirectional"))
    )
    (net (code "97") (name "unconnected-(A1A-PG1-PadCN11_58)") (class "Default")
      (node (ref "A1") (pin "CN11_58") (pinfunction "PG1_CN11_58") (pintype "bidirectional"))
    )
    (net (code "98") (name "unconnected-(A1A-PG2-PadCN11_42)") (class "Default")
      (node (ref "A1") (pin "CN11_42") (pinfunction "PG2_CN11_42") (pintype "bidirectional"))
    )
    (net (code "99") (name "unconnected-(A1A-PG3-PadCN11_44)") (class "Default")
      (node (ref "A1") (pin "CN11_44") (pinfunction "PG3_CN11_44") (pintype "bidirectional"))
    )
    (net (code "100") (name "unconnected-(A1A-PG9-PadCN11_63)") (class "Default")
      (node (ref "A1") (pin "CN11_63") (pinfunction "PG9_CN11_63") (pintype "bidirectional"))
    )
    (net (code "101") (name "unconnected-(A1A-PG10-PadCN11_66)") (class "Default")
      (node (ref "A1") (pin "CN11_66") (pinfunction "PG10_CN11_66") (pintype "bidirectional"))
    )
    (net (code "102") (name "unconnected-(A1A-PG11-PadCN11_70)") (class "Default")
      (node (ref "A1") (pin "CN11_70") (pinfunction "PG11_CN11_70") (pintype "bidirectional"))
    )
    (net (code "103") (name "unconnected-(A1A-PG12-PadCN11_65)") (class "Default")
      (node (ref "A1") (pin "CN11_65") (pinfunction "PG12_CN11_65") (pintype "bidirectional"))
    )
    (net (code "104") (name "unconnected-(A1A-PG13-PadCN11_68)") (class "Default")
      (node (ref "A1") (pin "CN11_68") (pinfunction "PG13_CN11_68") (pintype "bidirectional"))
    )
    (net (code "105") (name "unconnected-(A1A-PG15-PadCN11_64)") (class "Default")
      (node (ref "A1") (pin "CN11_64") (pinfunction "PG15_CN11_64") (pintype "bidirectional"))
    )
    (net (code "106") (name "unconnected-(A1A-PH0-PadCN11_29)") (class "Default")
      (node (ref "A1") (pin "CN11_29") (pinfunction "PH0_CN11_29") (pintype "bidirectional"))
    )
    (net (code "107") (name "unconnected-(A1A-PH1-PadCN11_31)") (class "Default")
      (node (ref "A1") (pin "CN11_31") (pinfunction "PH1_CN11_31") (pintype "bidirectional"))
    )
    (net (code "108") (name "unconnected-(A1A-RESET_CN11-PadCN11_14)") (class "Default")
      (node (ref "A1") (pin "CN11_14") (pinfunction "RESET_CN11_CN11_14") (pintype "bidirectional"))
    )
    (net (code "109") (name "unconnected-(A1B-PA7-PadCN12_15)") (class "Default")
      (node (ref "A1") (pin "CN12_15") (pinfunction "PA7_CN12_15") (pintype "bidirectional"))
    )
    (net (code "110") (name "unconnected-(A1B-PA8-PadCN12_23)") (class "Default")
      (node (ref "A1") (pin "CN12_23") (pinfunction "PA8_CN12_23") (pintype "bidirectional"))
    )
    (net (code "111") (name "unconnected-(A1B-PA9-PadCN12_21)") (class "Default")
      (node (ref "A1") (pin "CN12_21") (pinfunction "PA9_CN12_21") (pintype "bidirectional"))
    )
    (net (code "112") (name "unconnected-(A1B-PA10-PadCN12_33)") (class "Default")
      (node (ref "A1") (pin "CN12_33") (pinfunction "PA10_CN12_33") (pintype "bidirectional"))
    )
    (net (code "113") (name "unconnected-(A1B-PA11-PadCN12_14)") (class "Default")
      (node (ref "A1") (pin "CN12_14") (pinfunction "PA11_CN12_14") (pintype "bidirectional"))
    )
    (net (code "114") (name "unconnected-(A1B-PA12-PadCN12_12)") (class "Default")
      (node (ref "A1") (pin "CN12_12") (pinfunction "PA12_CN12_12") (pintype "bidirectional"))
    )
    (net (code "115") (name "unconnected-(A1B-PB4-PadCN12_27)") (class "Default")
      (node (ref "A1") (pin "CN12_27") (pinfunction "PB4_CN12_27") (pintype "bidirectional"))
    )
    (net (code "116") (name "unconnected-(A1B-PB6-PadCN12_17)") (class "Default")
      (node (ref "A1") (pin "CN12_17") (pinfunction "PB6_CN12_17") (pintype "bidirectional"))
    )
    (net (code "117") (name "unconnected-(A1B-PB8-PadCN12_3)") (class "Default")
      (node (ref "A1") (pin "CN12_3") (pinfunction "PB8_CN12_3") (pintype "bidirectional"))
    )
    (net (code "118") (name "unconnected-(A1B-PB9-PadCN12_5)") (class "Default")
      (node (ref "A1") (pin "CN12_5") (pinfunction "PB9_CN12_5") (pintype "bidirectional"))
    )
    (net (code "119") (name "unconnected-(A1B-PB10-PadCN12_25)") (class "Default")
      (node (ref "A1") (pin "CN12_25") (pinfunction "PB10_CN12_25") (pintype "bidirectional"))
    )
    (net (code "120") (name "unconnected-(A1B-PB11-PadCN12_18)") (class "Default")
      (node (ref "A1") (pin "CN12_18") (pinfunction "PB11_CN12_18") (pintype "bidirectional"))
    )
    (net (code "121") (name "unconnected-(A1B-PB12-PadCN12_16)") (class "Default")
      (node (ref "A1") (pin "CN12_16") (pinfunction "PB12_CN12_16") (pintype "bidirectional"))
    )
    (net (code "122") (name "unconnected-(A1B-PB13-PadCN12_30)") (class "Default")
      (node (ref "A1") (pin "CN12_30") (pinfunction "PB13_CN12_30") (pintype "bidirectional"))
    )
    (net (code "123") (name "unconnected-(A1B-PB14-PadCN12_28)") (class "Default")
      (node (ref "A1") (pin "CN12_28") (pinfunction "PB14_CN12_28") (pintype "bidirectional"))
    )
    (net (code "124") (name "unconnected-(A1B-PB15-PadCN12_26)") (class "Default")
      (node (ref "A1") (pin "CN12_26") (pinfunction "PB15_CN12_26") (pintype "bidirectional"))
    )
    (net (code "125") (name "unconnected-(A1B-PC4-PadCN12_34)") (class "Default")
      (node (ref "A1") (pin "CN12_34") (pinfunction "PC4_CN12_34") (pintype "bidirectional"))
    )
    (net (code "126") (name "unconnected-(A1B-PC5-PadCN12_6)") (class "Default")
      (node (ref "A1") (pin "CN12_6") (pinfunction "PC5_CN12_6") (pintype "bidirectional"))
    )
    (net (code "127") (name "unconnected-(A1B-PC6-PadCN12_4)") (class "Default")
      (node (ref "A1") (pin "CN12_4") (pinfunction "PC6_CN12_4") (pintype "bidirectional"))
    )
    (net (code "128") (name "unconnected-(A1B-PC7-PadCN12_19)") (class "Default")
      (node (ref "A1") (pin "CN12_19") (pinfunction "PC7_CN12_19") (pintype "bidirectional"))
    )
    (net (code "129") (name "unconnected-(A1B-PD10-PadCN12_65)") (class "Default")
      (node (ref "A1") (pin "CN12_65") (pinfunction "PD10_CN12_65") (pintype "bidirectional"))
    )
    (net (code "130") (name "unconnected-(A1B-PD11-PadCN12_45)") (class "Default")
      (node (ref "A1") (pin "CN12_45") (pinfunction "PD11_CN12_45") (pintype "bidirectional"))
    )
    (net (code "131") (name "unconnected-(A1B-PD12-PadCN12_43)") (class "Default")
      (node (ref "A1") (pin "CN12_43") (pinfunction "PD12_CN12_43") (pintype "bidirectional"))
    )
    (net (code "132") (name "unconnected-(A1B-PD13-PadCN12_41)") (class "Default")
      (node (ref "A1") (pin "CN12_41") (pinfunction "PD13_CN12_41") (pintype "bidirectional"))
    )
    (net (code "133") (name "unconnected-(A1B-PD14-PadCN12_46)") (class "Default")
      (node (ref "A1") (pin "CN12_46") (pinfunction "PD14_CN12_46") (pintype "bidirectional"))
    )
    (net (code "134") (name "unconnected-(A1B-PD15-PadCN12_48)") (class "Default")
      (node (ref "A1") (pin "CN12_48") (pinfunction "PD15_CN12_48") (pintype "bidirectional"))
    )
    (net (code "135") (name "unconnected-(A1B-PE0-PadCN12_64)") (class "Default")
      (node (ref "A1") (pin "CN12_64") (pinfunction "PE0_CN12_64") (pintype "bidirectional"))
    )
    (net (code "136") (name "unconnected-(A1B-PE7-PadCN12_44)") (class "Default")
      (node (ref "A1") (pin "CN12_44") (pinfunction "PE7_CN12_44") (pintype "bidirectional"))
    )
    (net (code "137") (name "unconnected-(A1B-PE9-PadCN12_52)") (class "Default")
      (node (ref "A1") (pin "CN12_52") (pinfunction "PE9_CN12_52") (pintype "bidirectional"))
    )
    (net (code "138") (name "unconnected-(A1B-PE10-PadCN12_47)") (class "Default")
      (node (ref "A1") (pin "CN12_47") (pinfunction "PE10_CN12_47") (pintype "bidirectional"))
    )
    (net (code "139") (name "unconnected-(A1B-PE11-PadCN12_56)") (class "Default")
      (node (ref "A1") (pin "CN12_56") (pinfunction "PE11_CN12_56") (pintype "bidirectional"))
    )
    (net (code "140") (name "unconnected-(A1B-PE12-PadCN12_49)") (class "Default")
      (node (ref "A1") (pin "CN12_49") (pinfunction "PE12_CN12_49") (pintype "bidirectional"))
    )
    (net (code "141") (name "unconnected-(A1B-PE13-PadCN12_55)") (class "Default")
      (node (ref "A1") (pin "CN12_55") (pinfunction "PE13_CN12_55") (pintype "bidirectional"))
    )
    (net (code "142") (name "unconnected-(A1B-PE14-PadCN12_51)") (class "Default")
      (node (ref "A1") (pin "CN12_51") (pinfunction "PE14_CN12_51") (pintype "bidirectional"))
    )
    (net (code "143") (name "unconnected-(A1B-PE15-PadCN12_53)") (class "Default")
      (node (ref "A1") (pin "CN12_53") (pinfunction "PE15_CN12_53") (pintype "bidirectional"))
    )
    (net (code "144") (name "unconnected-(A1B-PF3-PadCN12_58)") (class "Default")
      (node (ref "A1") (pin "CN12_58") (pinfunction "PF3_CN12_58") (pintype "bidirectional"))
    )
    (net (code "145") (name "unconnected-(A1B-PF4-PadCN12_38)") (class "Default")
      (node (ref "A1") (pin "CN12_38") (pinfunction "PF4_CN12_38") (pintype "bidirectional"))
    )
    (net (code "146") (name "unconnected-(A1B-PF5-PadCN12_36)") (class "Default")
      (node (ref "A1") (pin "CN12_36") (pinfunction "PF5_CN12_36") (pintype "bidirectional"))
    )
    (net (code "147") (name "unconnected-(A1B-PF11-PadCN12_62)") (class "Default")
      (node (ref "A1") (pin "CN12_62") (pinfunction "PF11_CN12_62") (pintype "bidirectional"))
    )
    (net (code "148") (name "unconnected-(A1B-PF13-PadCN12_57)") (class "Default")
      (node (ref "A1") (pin "CN12_57") (pinfunction "PF13_CN12_57") (pintype "bidirectional"))
    )
    (net (code "149") (name "unconnected-(A1B-PF14-PadCN12_50)") (class "Default")
      (node (ref "A1") (pin "CN12_50") (pinfunction "PF14_CN12_50") (pintype "bidirectional"))
    )
    (net (code "150") (name "unconnected-(A1B-PF15-PadCN12_60)") (class "Default")
      (node (ref "A1") (pin "CN12_60") (pinfunction "PF15_CN12_60") (pintype "bidirectional"))
    )
    (net (code "151") (name "unconnected-(A1B-PG4-PadCN12_69)") (class "Default")
      (node (ref "A1") (pin "CN12_69") (pinfunction "PG4_CN12_69") (pintype "bidirectional"))
    )
    (net (code "152") (name "unconnected-(A1B-PG5-PadCN12_68)") (class "Default")
      (node (ref "A1") (pin "CN12_68") (pinfunction "PG5_CN12_68") (pintype "bidirectional"))
    )
    (net (code "153") (name "unconnected-(A1B-PG6-PadCN12_70)") (class "Default")
      (node (ref "A1") (pin "CN12_70") (pinfunction "PG6_CN12_70") (pintype "bidirectional"))
    )
    (net (code "154") (name "unconnected-(A1B-PG7-PadCN12_67)") (class "Default")
      (node (ref "A1") (pin "CN12_67") (pinfunction "PG7_CN12_67") (pintype "bidirectional"))
    )
    (net (code "155") (name "unconnected-(A1B-PG8-PadCN12_66)") (class "Default")
      (node (ref "A1") (pin "CN12_66") (pinfunction "PG8_CN12_66") (pintype "bidirectional"))
    )
    (net (code "156") (name "unconnected-(A1B-PG14-PadCN12_61)") (class "Default")
      (node (ref "A1") (pin "CN12_61") (pinfunction "PG14_CN12_61") (pintype "bidirectional"))
    )
    (net (code "157") (name "unconnected-(A1C-D43{slash}SDMMC_D0-PadCN8_2)") (class "Default")
      (node (ref "A1") (pin "CN8_2") (pinfunction "D43/SDMMC_D0_CN8_2") (pintype "bidirectional"))
    )
    (net (code "158") (name "unconnected-(A1C-D44{slash}SDMMC_D1{slash}I2S_A_CKIN-PadCN8_4)") (class "Default")
      (node (ref "A1") (pin "CN8_4") (pinfunction "D44/SDMMC_D1/I2S_A_CKIN_CN8_4") (pintype "bidirectional"))
    )
    (net (code "159") (name "unconnected-(A1C-D45{slash}SDMMC_D2-PadCN8_6)") (class "Default")
      (node (ref "A1") (pin "CN8_6") (pinfunction "D45/SDMMC_D2_CN8_6") (pintype "bidirectional"))
    )
    (net (code "160") (name "unconnected-(A1C-D46{slash}SDMMC_D3-PadCN8_8)") (class "Default")
      (node (ref "A1") (pin "CN8_8") (pinfunction "D46/SDMMC_D3_CN8_8") (pintype "bidirectional"))
    )
    (net (code "161") (name "unconnected-(A1C-D47{slash}SDMMC_CK-PadCN8_10)") (class "Default")
      (node (ref "A1") (pin "CN8_10") (pinfunction "D47/SDMMC_CK_CN8_10") (pintype "bidirectional"))
    )
    (net (code "162") (name "unconnected-(A1C-D48{slash}SDMMC_CMD-PadCN8_12)") (class "Default")
      (node (ref "A1") (pin "CN8_12") (pinfunction "D48/SDMMC_CMD_CN8_12") (pintype "bidirectional"))
    )
    (net (code "163") (name "unconnected-(A1C-D49{slash}IO-PadCN8_14)") (class "Default")
      (node (ref "A1") (pin "CN8_14") (pinfunction "D49/IO_CN8_14") (pintype "bidirectional"))
    )
    (net (code "164") (name "unconnected-(A1C-D50{slash}IO-PadCN8_16)") (class "Default")
      (node (ref "A1") (pin "CN8_16") (pinfunction "D50/IO_CN8_16") (pintype "bidirectional"))
    )
    (net (code "165") (name "unconnected-(A1C-IOREF_CN8-PadCN8_3)") (class "Default")
      (node (ref "A1") (pin "CN8_3") (pinfunction "IOREF_CN8_CN8_3") (pintype "bidirectional"))
    )
    (net (code "166") (name "unconnected-(A1C-RESET_CN8-PadCN8_5)") (class "Default")
      (node (ref "A1") (pin "CN8_5") (pinfunction "RESET_CN8_CN8_5") (pintype "bidirectional"))
    )
    (net (code "167") (name "unconnected-(A1D-A0{slash}ADC123_IN3-PadCN9_1)") (class "Default")
      (node (ref "A1") (pin "CN9_1") (pinfunction "A0/ADC123_IN3_CN9_1") (pintype "input"))
    )
    (net (code "168") (name "unconnected-(A1D-A1{slash}ADC123_IN10-PadCN9_3)") (class "Default")
      (node (ref "A1") (pin "CN9_3") (pinfunction "A1/ADC123_IN10_CN9_3") (pintype "input"))
    )
    (net (code "169") (name "unconnected-(A1D-A2{slash}ADC123_IN13-PadCN9_5)") (class "Default")
      (node (ref "A1") (pin "CN9_5") (pinfunction "A2/ADC123_IN13_CN9_5") (pintype "input"))
    )
    (net (code "170") (name "unconnected-(A1D-A3{slash}ADC3_IN9-PadCN9_7)") (class "Default")
      (node (ref "A1") (pin "CN9_7") (pinfunction "A3/ADC3_IN9_CN9_7") (pintype "input"))
    )
    (net (code "171") (name "unconnected-(A1D-A4{slash}ADC3_IN15{slash}I2C1_SDA-PadCN9_9)") (class "Default")
      (node (ref "A1") (pin "CN9_9") (pinfunction "A4/ADC3_IN15/I2C1_SDA_CN9_9") (pintype "input"))
    )
    (net (code "172") (name "unconnected-(A1D-A5{slash}ADC3_IN8{slash}I2C1_SCL-PadCN9_11)") (class "Default")
      (node (ref "A1") (pin "CN9_11") (pinfunction "A5/ADC3_IN8/I2C1_SCL_CN9_11") (pintype "input"))
    )
    (net (code "173") (name "unconnected-(A1D-D51{slash}USART_B_SCLK-PadCN9_2)") (class "Default")
      (node (ref "A1") (pin "CN9_2") (pinfunction "D51/USART_B_SCLK_CN9_2") (pintype "bidirectional"))
    )
    (net (code "174") (name "unconnected-(A1D-D52{slash}USART_B_RX-PadCN9_4)") (class "Default")
      (node (ref "A1") (pin "CN9_4") (pinfunction "D52/USART_B_RX_CN9_4") (pintype "bidirectional"))
    )
    (net (code "175") (name "unconnected-(A1D-D53{slash}USART_B_TX-PadCN9_6)") (class "Default")
      (node (ref "A1") (pin "CN9_6") (pinfunction "D53/USART_B_TX_CN9_6") (pintype "bidirectional"))
    )
    (net (code "176") (name "unconnected-(A1D-D54{slash}USART_B_RTS-PadCN9_8)") (class "Default")
      (node (ref "A1") (pin "CN9_8") (pinfunction "D54/USART_B_RTS_CN9_8") (pintype "bidirectional"))
    )
    (net (code "177") (name "unconnected-(A1D-D55{slash}USART_B_CTS-PadCN9_10)") (class "Default")
      (node (ref "A1") (pin "CN9_10") (pinfunction "D55/USART_B_CTS_CN9_10") (pintype "bidirectional"))
    )
    (net (code "178") (name "unconnected-(A1D-D56{slash}SAI_A_MCLK-PadCN9_14)") (class "Default")
      (node (ref "A1") (pin "CN9_14") (pinfunction "D56/SAI_A_MCLK_CN9_14") (pintype "bidirectional"))
    )
    (net (code "179") (name "unconnected-(A1D-D57{slash}SAI_A_FS-PadCN9_16)") (class "Default")
      (node (ref "A1") (pin "CN9_16") (pinfunction "D57/SAI_A_FS_CN9_16") (pintype "bidirectional"))
    )
    (net (code "180") (name "unconnected-(A1D-D58{slash}SAI_A_SCK-PadCN9_18)") (class "Default")
      (node (ref "A1") (pin "CN9_18") (pinfunction "D58/SAI_A_SCK_CN9_18") (pintype "bidirectional"))
    )
    (net (code "181") (name "unconnected-(A1D-D59{slash}SAI_A_SD-PadCN9_20)") (class "Default")
      (node (ref "A1") (pin "CN9_20") (pinfunction "D59/SAI_A_SD_CN9_20") (pintype "bidirectional"))
    )
    (net (code "182") (name "unconnected-(A1D-D60{slash}SAI_B_SD-PadCN9_22)") (class "Default")
      (node (ref "A1") (pin "CN9_22") (pinfunction "D60/SAI_B_SD_CN9_22") (pintype "bidirectional"))
    )
    (net (code "183") (name "unconnected-(A1D-D61{slash}SAI_B_SCK-PadCN9_24)") (class "Default")
      (node (ref "A1") (pin "CN9_24") (pinfunction "D61/SAI_B_SCK_CN9_24") (pintype "bidirectional"))
    )
    (net (code "184") (name "unconnected-(A1D-D62{slash}SAI_B_MCLK-PadCN9_26)") (class "Default")
      (node (ref "A1") (pin "CN9_26") (pinfunction "D62/SAI_B_MCLK_CN9_26") (pintype "bidirectional"))
    )
    (net (code "185") (name "unconnected-(A1D-D63{slash}SAI_B_FS-PadCN9_28)") (class "Default")
      (node (ref "A1") (pin "CN9_28") (pinfunction "D63/SAI_B_FS_CN9_28") (pintype "bidirectional"))
    )
    (net (code "186") (name "unconnected-(A1D-D64{slash}IO-PadCN9_30)") (class "Default")
      (node (ref "A1") (pin "CN9_30") (pinfunction "D64/IO_CN9_30") (pintype "bidirectional"))
    )
    (net (code "187") (name "unconnected-(A1D-D65{slash}IO-PadCN9_29)") (class "Default")
      (node (ref "A1") (pin "CN9_29") (pinfunction "D65/IO_CN9_29") (pintype "bidirectional"))
    )
    (net (code "188") (name "unconnected-(A1D-D66{slash}CAN_TX-PadCN9_27)") (class "Default")
      (node (ref "A1") (pin "CN9_27") (pinfunction "D66/CAN_TX_CN9_27") (pintype "output"))
    )
    (net (code "189") (name "unconnected-(A1D-D67{slash}CAN_RX-PadCN9_25)") (class "Default")
      (node (ref "A1") (pin "CN9_25") (pinfunction "D67/CAN_RX_CN9_25") (pintype "input"))
    )
    (net (code "190") (name "unconnected-(A1D-D68{slash}I2C_B_SDA-PadCN9_21)") (class "Default")
      (node (ref "A1") (pin "CN9_21") (pinfunction "D68/I2C_B_SDA_CN9_21") (pintype "bidirectional"))
    )
    (net (code "191") (name "unconnected-(A1D-D69{slash}I2C_B_SCL-PadCN9_19)") (class "Default")
      (node (ref "A1") (pin "CN9_19") (pinfunction "D69/I2C_B_SCL_CN9_19") (pintype "bidirectional"))
    )
    (net (code "192") (name "unconnected-(A1D-D70{slash}I2C_B_SMBA-PadCN9_17)") (class "Default")
      (node (ref "A1") (pin "CN9_17") (pinfunction "D70/I2C_B_SMBA_CN9_17") (pintype "bidirectional"))
    )
    (net (code "193") (name "unconnected-(A1D-D71{slash}IO-PadCN9_15)") (class "Default")
      (node (ref "A1") (pin "CN9_15") (pinfunction "D71/IO_CN9_15") (pintype "bidirectional"))
    )
    (net (code "194") (name "unconnected-(A1D-D72{slash}NC-PadCN9_13)") (class "Default")
      (node (ref "A1") (pin "CN9_13") (pinfunction "D72/NC_CN9_13") (pintype "bidirectional"))
    )
    (net (code "195") (name "unconnected-(A1E-D8{slash}IO-PadCN7_20)") (class "Default")
      (node (ref "A1") (pin "CN7_20") (pinfunction "D8/IO_CN7_20") (pintype "bidirectional"))
    )
    (net (code "196") (name "unconnected-(A1E-D9{slash}TIMER_B_PWM2-PadCN7_18)") (class "Default")
      (node (ref "A1") (pin "CN7_18") (pinfunction "D9/TIMER_B_PWM2_CN7_18") (pintype "bidirectional"))
    )
    (net (code "197") (name "unconnected-(A1E-D10{slash}SPI_A_CS{slash}TIM_B_PWM3-PadCN7_16)") (class "Default")
      (node (ref "A1") (pin "CN7_16") (pinfunction "D10/SPI_A_CS/TIM_B_PWM3_CN7_16") (pintype "bidirectional"))
    )
    (net (code "198") (name "unconnected-(A1E-D11{slash}SPI_A_MOSI{slash}TIM_E_PWM1-PadCN7_14)") (class "Default")
      (node (ref "A1") (pin "CN7_14") (pinfunction "D11/SPI_A_MOSI/TIM_E_PWM1_CN7_14") (pintype "bidirectional"))
    )
    (net (code "199") (name "unconnected-(A1E-D12{slash}SPI_A_MISO-PadCN7_12)") (class "Default")
      (node (ref "A1") (pin "CN7_12") (pinfunction "D12/SPI_A_MISO_CN7_12") (pintype "bidirectional"))
    )
    (net (code "200") (name "unconnected-(A1E-D13{slash}SPI_A_SCK-PadCN7_10)") (class "Default")
      (node (ref "A1") (pin "CN7_10") (pinfunction "D13/SPI_A_SCK_CN7_10") (pintype "bidirectional"))
    )
    (net (code "201") (name "unconnected-(A1E-D14{slash}I2C_A_SDA-PadCN7_4)") (class "Default")
      (node (ref "A1") (pin "CN7_4") (pinfunction "D14/I2C_A_SDA_CN7_4") (pintype "bidirectional"))
    )
    (net (code "202") (name "unconnected-(A1E-D15{slash}I2C_A_SCL-PadCN7_2)") (class "Default")
      (node (ref "A1") (pin "CN7_2") (pinfunction "D15/I2C_A_SCL_CN7_2") (pintype "bidirectional"))
    )
    (net (code "203") (name "unconnected-(A1E-D16{slash}I2S_A_MCK-PadCN7_1)") (class "Default")
      (node (ref "A1") (pin "CN7_1") (pinfunction "D16/I2S_A_MCK_CN7_1") (pintype "bidirectional"))
    )
    (net (code "204") (name "unconnected-(A1E-D17{slash}I2S_A_SD-PadCN7_3)") (class "Default")
      (node (ref "A1") (pin "CN7_3") (pinfunction "D17/I2S_A_SD_CN7_3") (pintype "bidirectional"))
    )
    (net (code "205") (name "unconnected-(A1E-D18{slash}I2S_A_CK-PadCN7_5)") (class "Default")
      (node (ref "A1") (pin "CN7_5") (pinfunction "D18/I2S_A_CK_CN7_5") (pintype "bidirectional"))
    )
    (net (code "206") (name "unconnected-(A1E-D19{slash}I2S_A_WS-PadCN7_7)") (class "Default")
      (node (ref "A1") (pin "CN7_7") (pinfunction "D19/I2S_A_WS_CN7_7") (pintype "bidirectional"))
    )
    (net (code "207") (name "unconnected-(A1E-D20{slash}I2S_B_WS-PadCN7_9)") (class "Default")
      (node (ref "A1") (pin "CN7_9") (pinfunction "D20/I2S_B_WS_CN7_9") (pintype "bidirectional"))
    )
    (net (code "208") (name "unconnected-(A1E-D21{slash}I2S_B_MCK-PadCN7_11)") (class "Default")
      (node (ref "A1") (pin "CN7_11") (pinfunction "D21/I2S_B_MCK_CN7_11") (pintype "bidirectional"))
    )
    (net (code "209") (name "unconnected-(A1E-D22{slash}I2S_B_SD{slash}SPI_B_MOSI-PadCN7_13)") (class "Default")
      (node (ref "A1") (pin "CN7_13") (pinfunction "D22/I2S_B_SD/SPI_B_MOSI_CN7_13") (pintype "bidirectional"))
    )
    (net (code "210") (name "unconnected-(A1E-D23{slash}I2S_B_CK{slash}SPI_B_SCK-PadCN7_15)") (class "Default")
      (node (ref "A1") (pin "CN7_15") (pinfunction "D23/I2S_B_CK/SPI_B_SCK_CN7_15") (pintype "bidirectional"))
    )
    (net (code "211") (name "unconnected-(A1E-D24{slash}SPI_B_NSS-PadCN7_17)") (class "Default")
      (node (ref "A1") (pin "CN7_17") (pinfunction "D24/SPI_B_NSS_CN7_17") (pintype "bidirectional"))
    )
    (net (code "212") (name "unconnected-(A1E-D25{slash}SPI_B_MISO-PadCN7_19)") (class "Default")
      (node (ref "A1") (pin "CN7_19") (pinfunction "D25/SPI_B_MISO_CN7_19") (pintype "bidirectional"))
    )
    (net (code "213") (name "unconnected-(A1F-A6{slash}ADC_A_IN-PadCN10_7)") (class "Default")
      (node (ref "A1") (pin "CN10_7") (pinfunction "A6/ADC_A_IN_CN10_7") (pintype "input"))
    )
    (net (code "214") (name "unconnected-(A1F-A7{slash}ADC_B_IN-PadCN10_9)") (class "Default")
      (node (ref "A1") (pin "CN10_9") (pinfunction "A7/ADC_B_IN_CN10_9") (pintype "input"))
    )
    (net (code "215") (name "unconnected-(A1F-A8{slash}ADC_C_IN-PadCN10_11)") (class "Default")
      (node (ref "A1") (pin "CN10_11") (pinfunction "A8/ADC_C_IN_CN10_11") (pintype "input"))
    )
    (net (code "216") (name "unconnected-(A1F-D0{slash}USART_A_RX-PadCN10_16)") (class "Default")
      (node (ref "A1") (pin "CN10_16") (pinfunction "D0/USART_A_RX_CN10_16") (pintype "input"))
    )
    (net (code "217") (name "unconnected-(A1F-D1{slash}USART_A_TX-PadCN10_14)") (class "Default")
      (node (ref "A1") (pin "CN10_14") (pinfunction "D1/USART_A_TX_CN10_14") (pintype "output"))
    )
    (net (code "218") (name "unconnected-(A1F-D2{slash}IO-PadCN10_12)") (class "Default")
      (node (ref "A1") (pin "CN10_12") (pinfunction "D2/IO_CN10_12") (pintype "bidirectional"))
    )
    (net (code "219") (name "unconnected-(A1F-D3{slash}TIMER_A_PWM3-PadCN10_10)") (class "Default")
      (node (ref "A1") (pin "CN10_10") (pinfunction "D3/TIMER_A_PWM3_CN10_10") (pintype "bidirectional"))
    )
    (net (code "220") (name "unconnected-(A1F-D4{slash}IO-PadCN10_8)") (class "Default")
      (node (ref "A1") (pin "CN10_8") (pinfunction "D4/IO_CN10_8") (pintype "bidirectional"))
    )
    (net (code "221") (name "unconnected-(A1F-D5{slash}TIMER_A_PWM2-PadCN10_6)") (class "Default")
      (node (ref "A1") (pin "CN10_6") (pinfunction "D5/TIMER_A_PWM2_CN10_6") (pintype "bidirectional"))
    )
    (net (code "222") (name "unconnected-(A1F-D6{slash}TIMER_A_PWM1-PadCN10_4)") (class "Default")
      (node (ref "A1") (pin "CN10_4") (pinfunction "D6/TIMER_A_PWM1_CN10_4") (pintype "bidirectional"))
    )
    (net (code "223") (name "unconnected-(A1F-D7{slash}IO-PadCN10_2)") (class "Default")
      (node (ref "A1") (pin "CN10_2") (pinfunction "D7/IO_CN10_2") (pintype "bidirectional"))
    )
    (net (code "224") (name "unconnected-(A1F-D26{slash}QSPI_CS-PadCN10_13)") (class "Default")
      (node (ref "A1") (pin "CN10_13") (pinfunction "D26/QSPI_CS_CN10_13") (pintype "bidirectional"))
    )
    (net (code "225") (name "unconnected-(A1F-D27{slash}QSPI_CLK-PadCN10_15)") (class "Default")
      (node (ref "A1") (pin "CN10_15") (pinfunction "D27/QSPI_CLK_CN10_15") (pintype "bidirectional"))
    )
    (net (code "226") (name "unconnected-(A1F-D28{slash}QSPI_BK1_IO3-PadCN10_19)") (class "Default")
      (node (ref "A1") (pin "CN10_19") (pinfunction "D28/QSPI_BK1_IO3_CN10_19") (pintype "bidirectional"))
    )
    (net (code "227") (name "unconnected-(A1F-D29{slash}QSPI_BK1_IO1-PadCN10_21)") (class "Default")
      (node (ref "A1") (pin "CN10_21") (pinfunction "D29/QSPI_BK1_IO1_CN10_21") (pintype "bidirectional"))
    )
    (net (code "228") (name "unconnected-(A1F-D30{slash}QSPI_BK1_IO0-PadCN10_23)") (class "Default")
      (node (ref "A1") (pin "CN10_23") (pinfunction "D30/QSPI_BK1_IO0_CN10_23") (pintype "bidirectional"))
    )
    (net (code "229") (name "unconnected-(A1F-D31{slash}QSPI_BK1_IO2-PadCN10_25)") (class "Default")
      (node (ref "A1") (pin "CN10_25") (pinfunction "D31/QSPI_BK1_IO2_CN10_25") (pintype "bidirectional"))
    )
    (net (code "230") (name "unconnected-(A1F-D32{slash}TIMER_C_PWM1-PadCN10_29)") (class "Default")
      (node (ref "A1") (pin "CN10_29") (pinfunction "D32/TIMER_C_PWM1_CN10_29") (pintype "bidirectional"))
    )
    (net (code "231") (name "unconnected-(A1F-D33{slash}TIMER_D_PWM1-PadCN10_31)") (class "Default")
      (node (ref "A1") (pin "CN10_31") (pinfunction "D33/TIMER_D_PWM1_CN10_31") (pintype "bidirectional"))
    )
    (net (code "232") (name "unconnected-(A1F-D34{slash}TIMER_B_ETR-PadCN10_33)") (class "Default")
      (node (ref "A1") (pin "CN10_33") (pinfunction "D34/TIMER_B_ETR_CN10_33") (pintype "bidirectional"))
    )
    (net (code "233") (name "unconnected-(A1F-D35{slash}TIMER_C_PWM3-PadCN10_34)") (class "Default")
      (node (ref "A1") (pin "CN10_34") (pinfunction "D35/TIMER_C_PWM3_CN10_34") (pintype "bidirectional"))
    )
    (net (code "234") (name "unconnected-(A1F-D36{slash}TIMER_C_PWM2-PadCN10_32)") (class "Default")
      (node (ref "A1") (pin "CN10_32") (pinfunction "D36/TIMER_C_PWM2_CN10_32") (pintype "bidirectional"))
    )
    (net (code "235") (name "unconnected-(A1F-D37{slash}TIMER_A_BKIN1-PadCN10_30)") (class "Default")
      (node (ref "A1") (pin "CN10_30") (pinfunction "D37/TIMER_A_BKIN1_CN10_30") (pintype "bidirectional"))
    )
    (net (code "236") (name "unconnected-(A1F-D38{slash}IO-PadCN10_28)") (class "Default")
      (node (ref "A1") (pin "CN10_28") (pinfunction "D38/IO_CN10_28") (pintype "bidirectional"))
    )
    (net (code "237") (name "unconnected-(A1F-D39{slash}TIMER_A_PWM3N-PadCN10_26)") (class "Default")
      (node (ref "A1") (pin "CN10_26") (pinfunction "D39/TIMER_A_PWM3N_CN10_26") (pintype "bidirectional"))
    )
    (net (code "238") (name "unconnected-(A1F-D40{slash}TIMER_A_PWM2N-PadCN10_24)") (class "Default")
      (node (ref "A1") (pin "CN10_24") (pinfunction "D40/TIMER_A_PWM2N_CN10_24") (pintype "bidirectional"))
    )
    (net (code "239") (name "unconnected-(A1F-D41{slash}TIMER_A_ETR-PadCN10_20)") (class "Default")
      (node (ref "A1") (pin "CN10_20") (pinfunction "D41/TIMER_A_ETR_CN10_20") (pintype "bidirectional"))
    )
    (net (code "240") (name "unconnected-(A1F-D42{slash}TIMER_A_PWM1N-PadCN10_18)") (class "Default")
      (node (ref "A1") (pin "CN10_18") (pinfunction "D42/TIMER_A_PWM1N_CN10_18") (pintype "bidirectional"))
    )
    (net (code "241") (name "unconnected-(J1-D+-Pad3)") (class "Default")
      (node (ref "J1") (pin "3") (pinfunction "D+_3") (pintype "bidirectional"))
    )
    (net (code "242") (name "unconnected-(J1-D--Pad2)") (class "Default")
      (node (ref "J1") (pin "2") (pinfunction "D-_2") (pintype "bidirectional"))
    )
    (net (code "243") (name "unconnected-(J1-ID-Pad4)") (class "Default")
      (node (ref "J1") (pin "4") (pinfunction "ID_4") (pintype "bidirectional"))
    )
  )
)
